# time-module.net
KiCad netlist of a schematic drawn in EAGLE
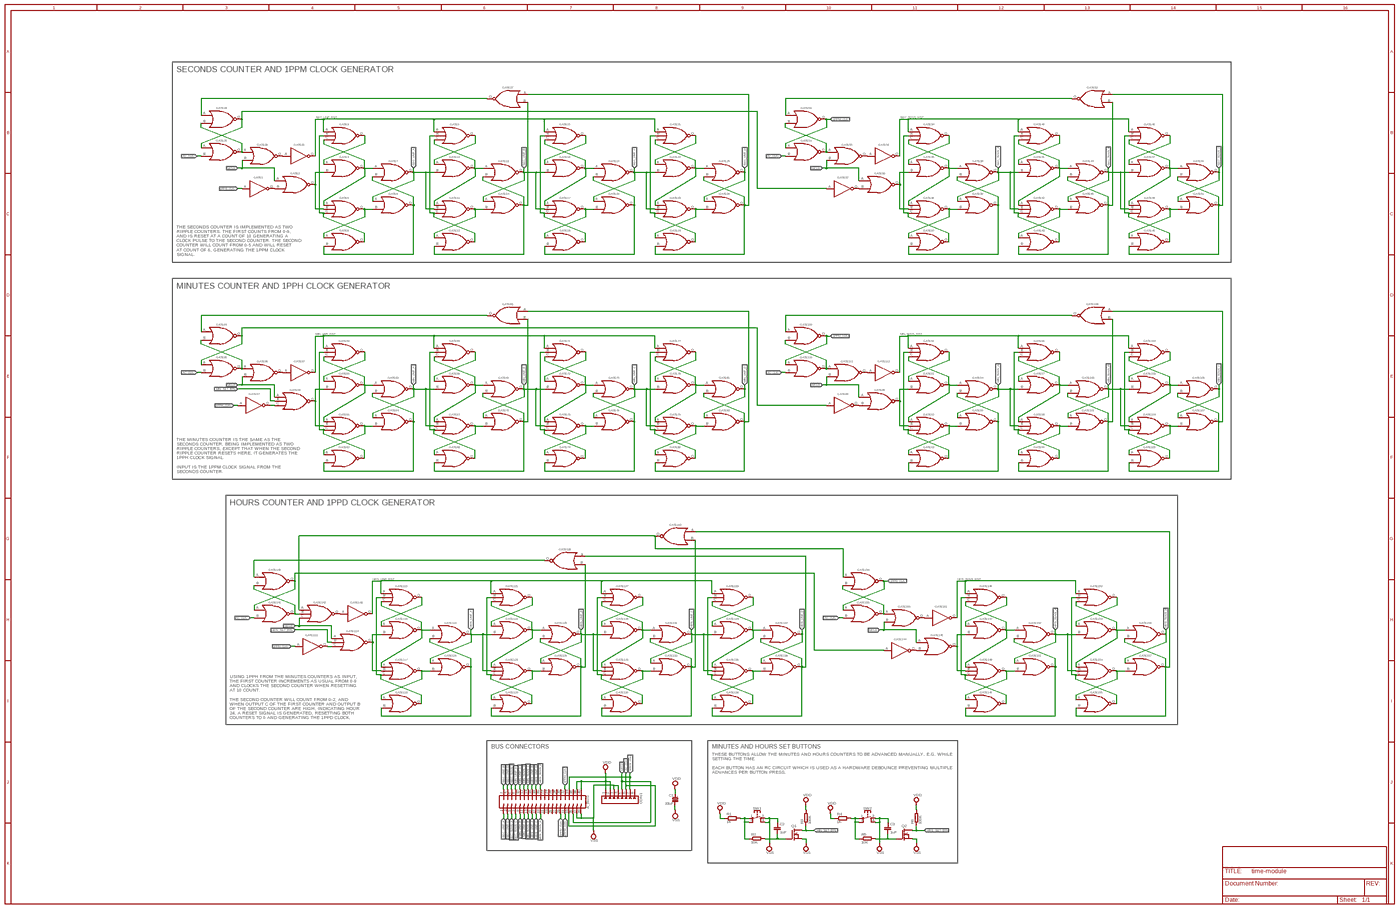
[diagram p0: schematic, sheet 1, overview]
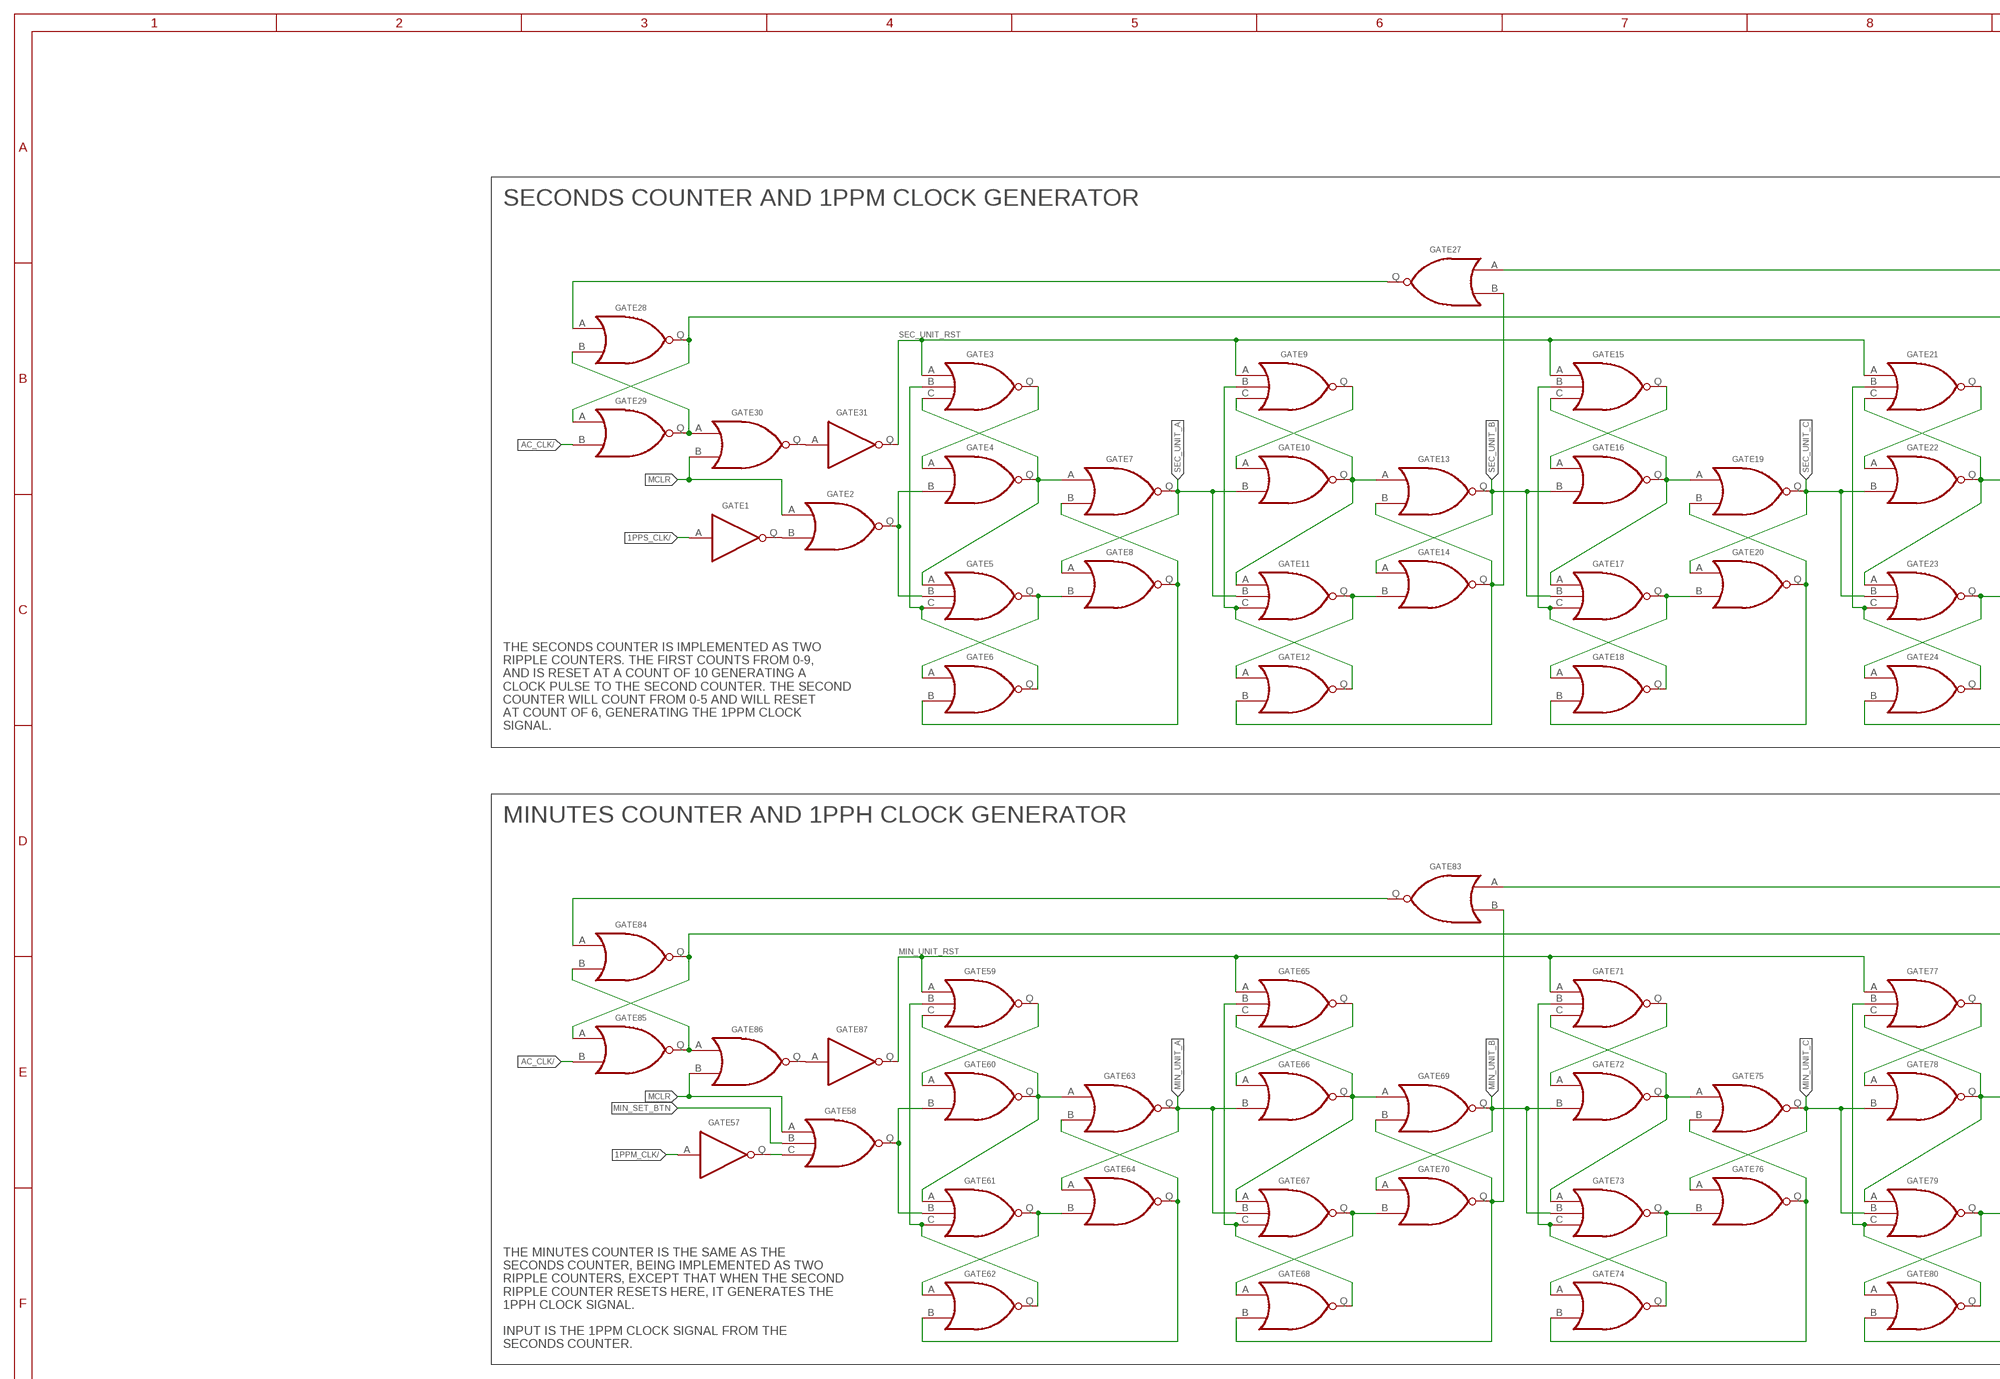
[diagram p1: schematic, sheet 1, part 1 of 4]
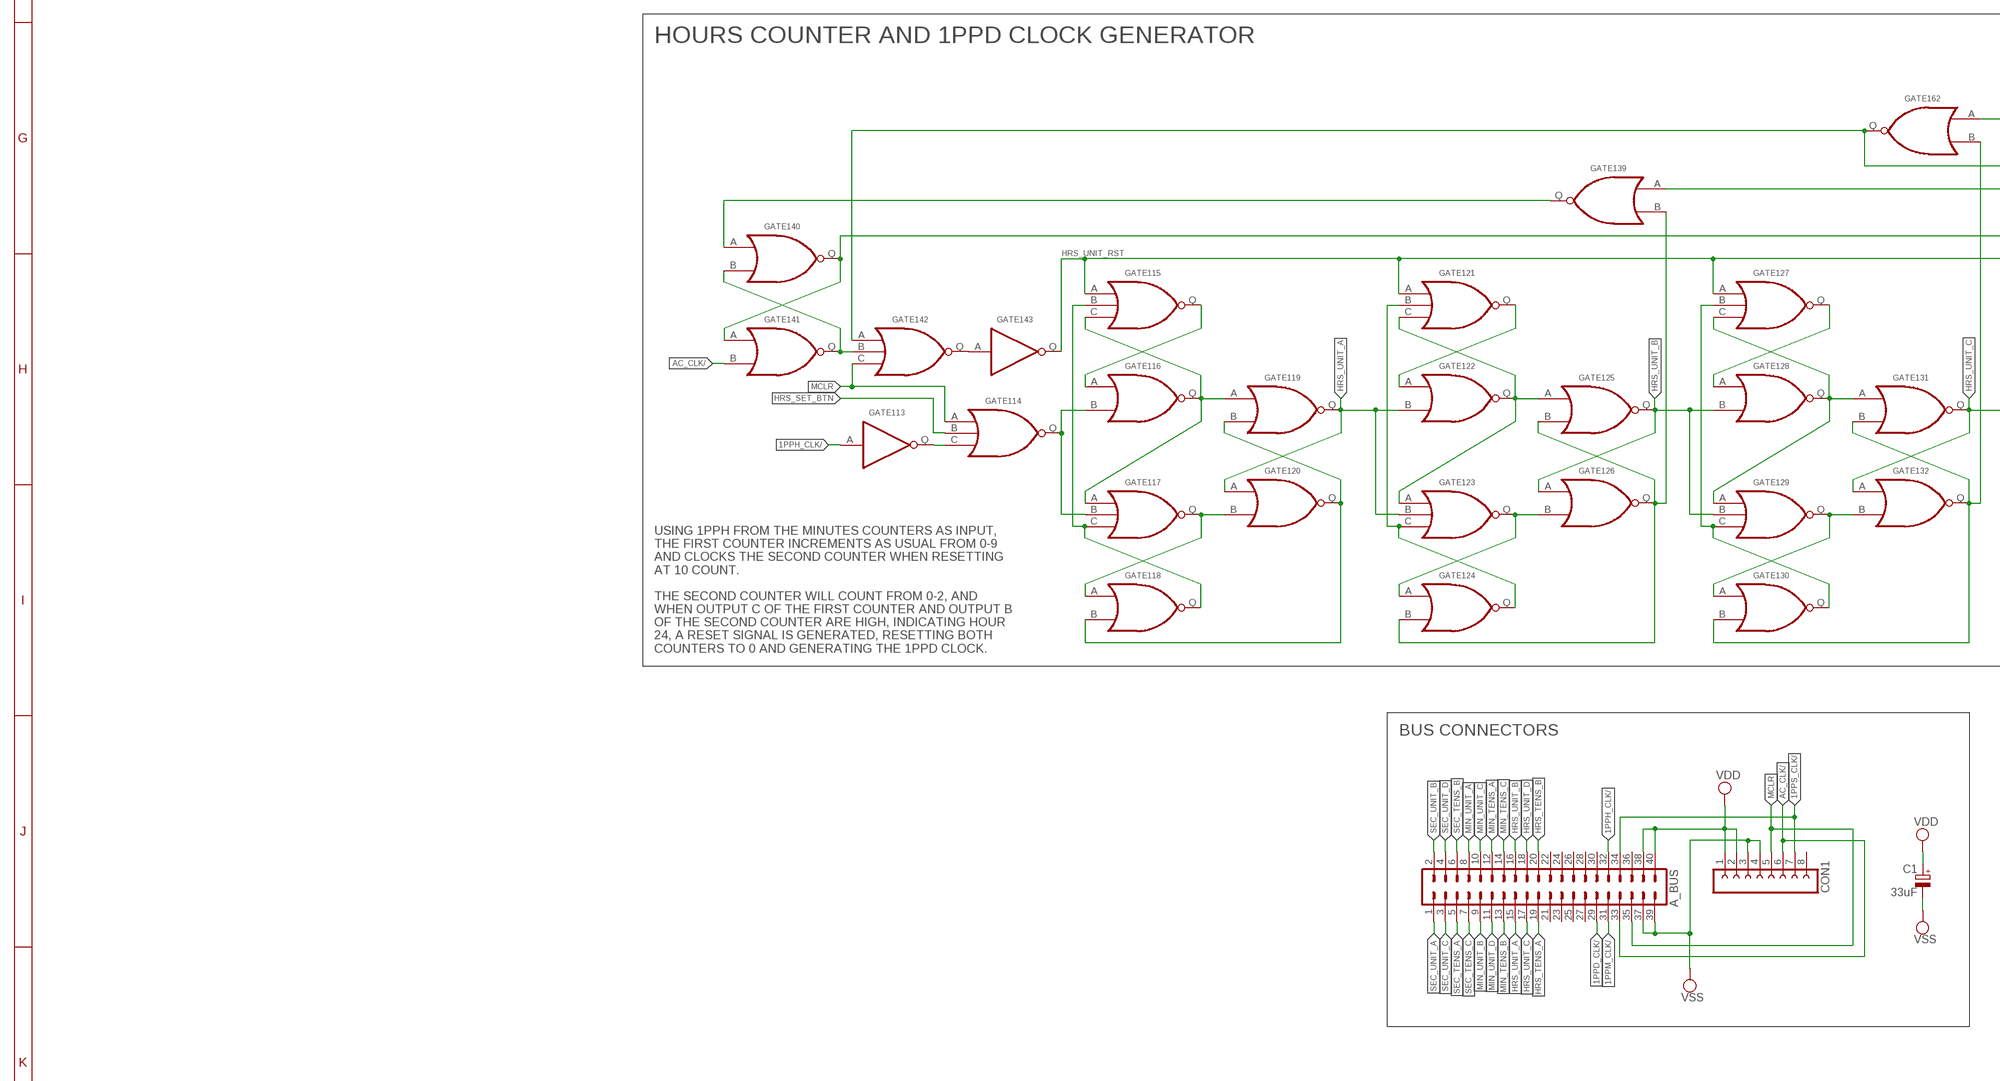
[diagram p2: schematic, sheet 1, part 2 of 4]
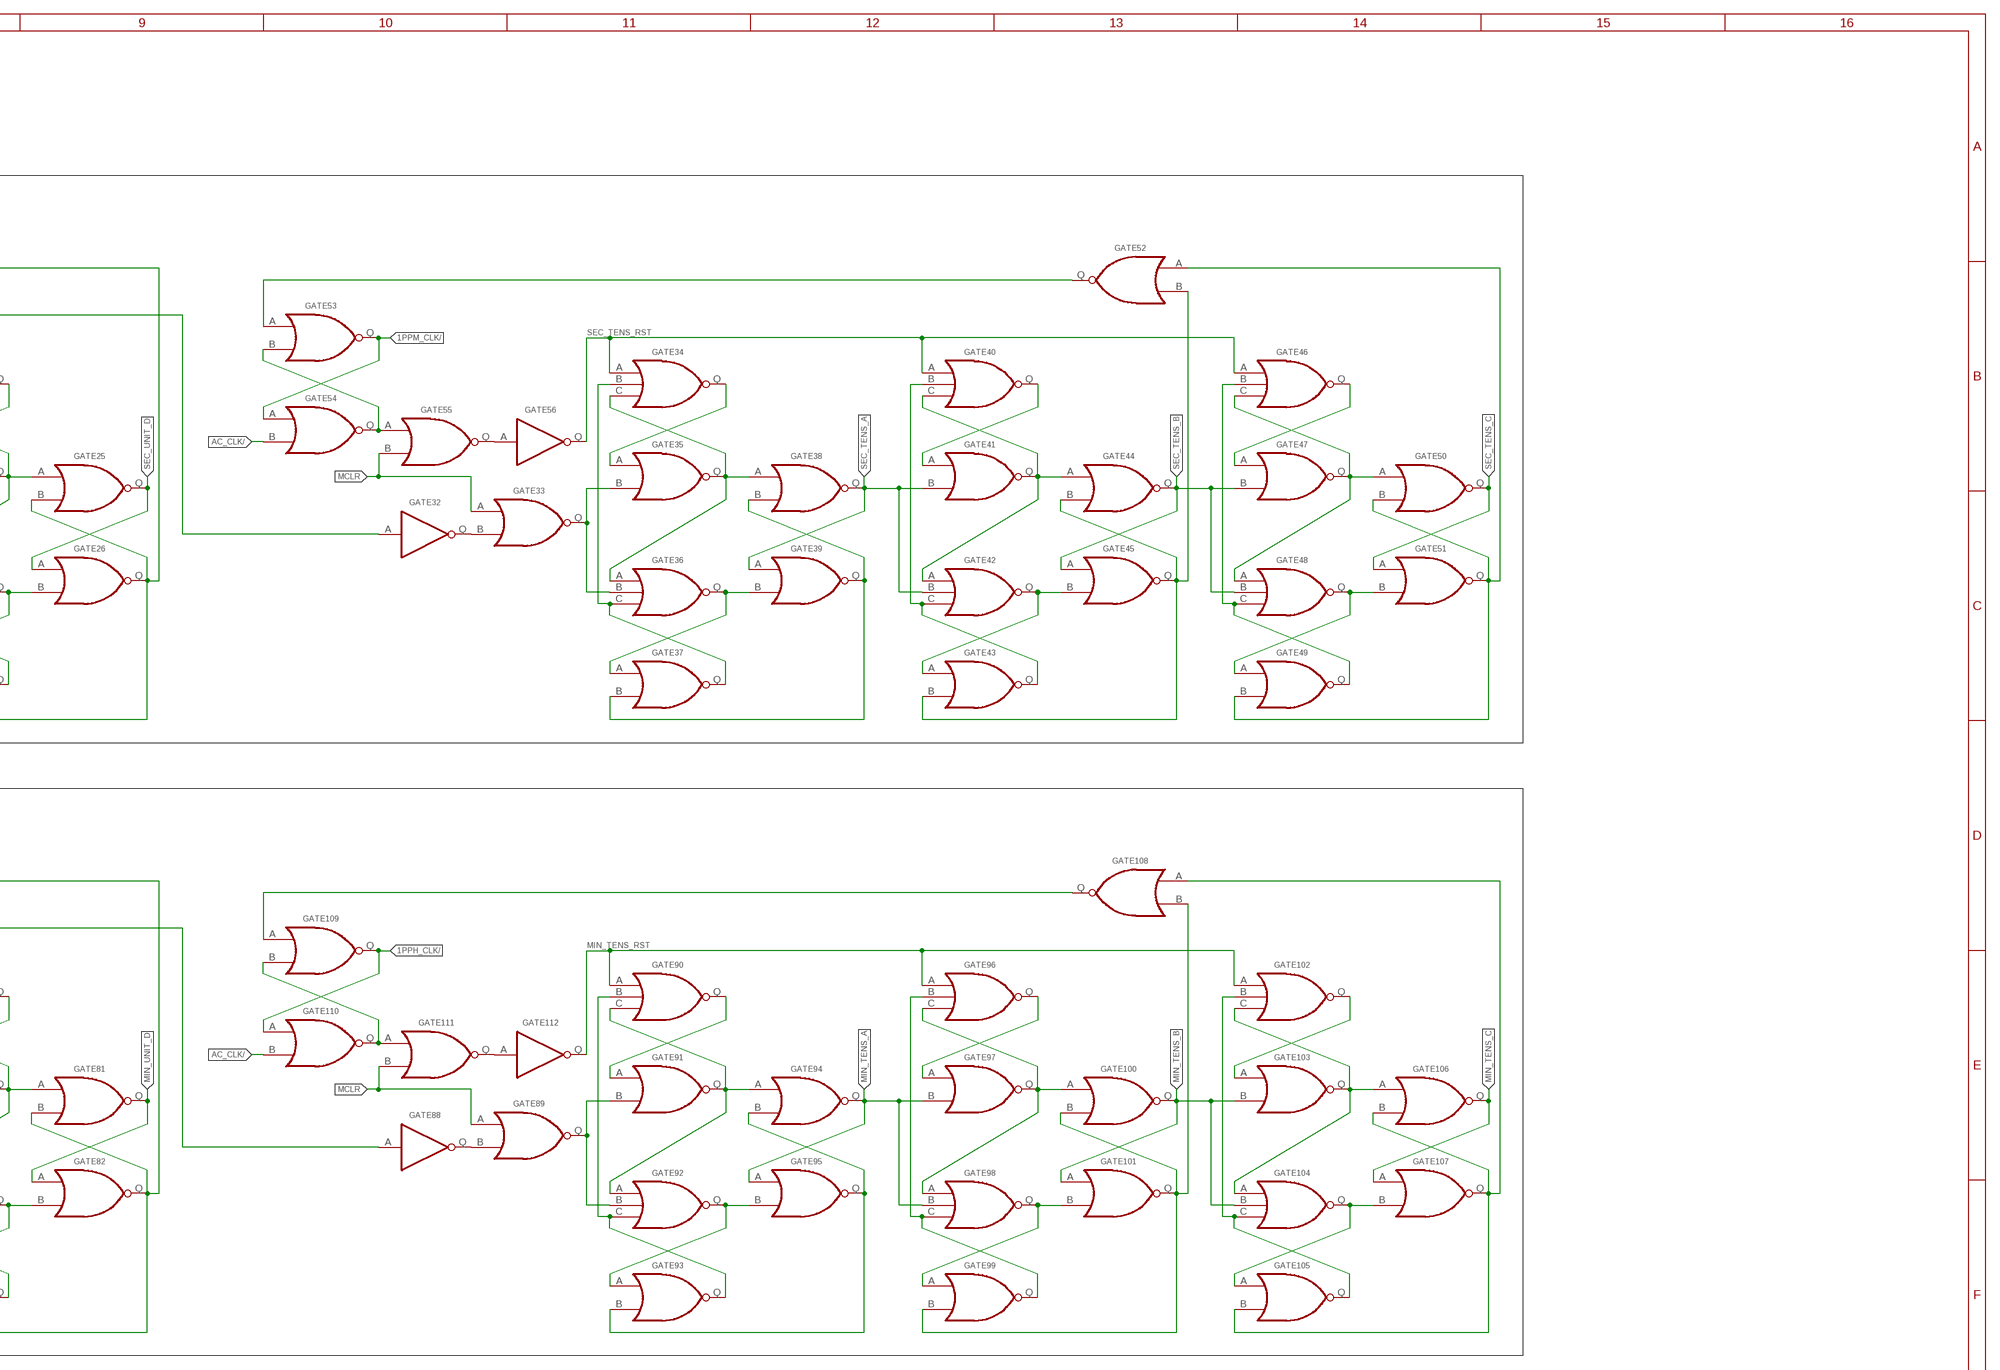
[diagram p3: schematic, sheet 1, part 3 of 4]
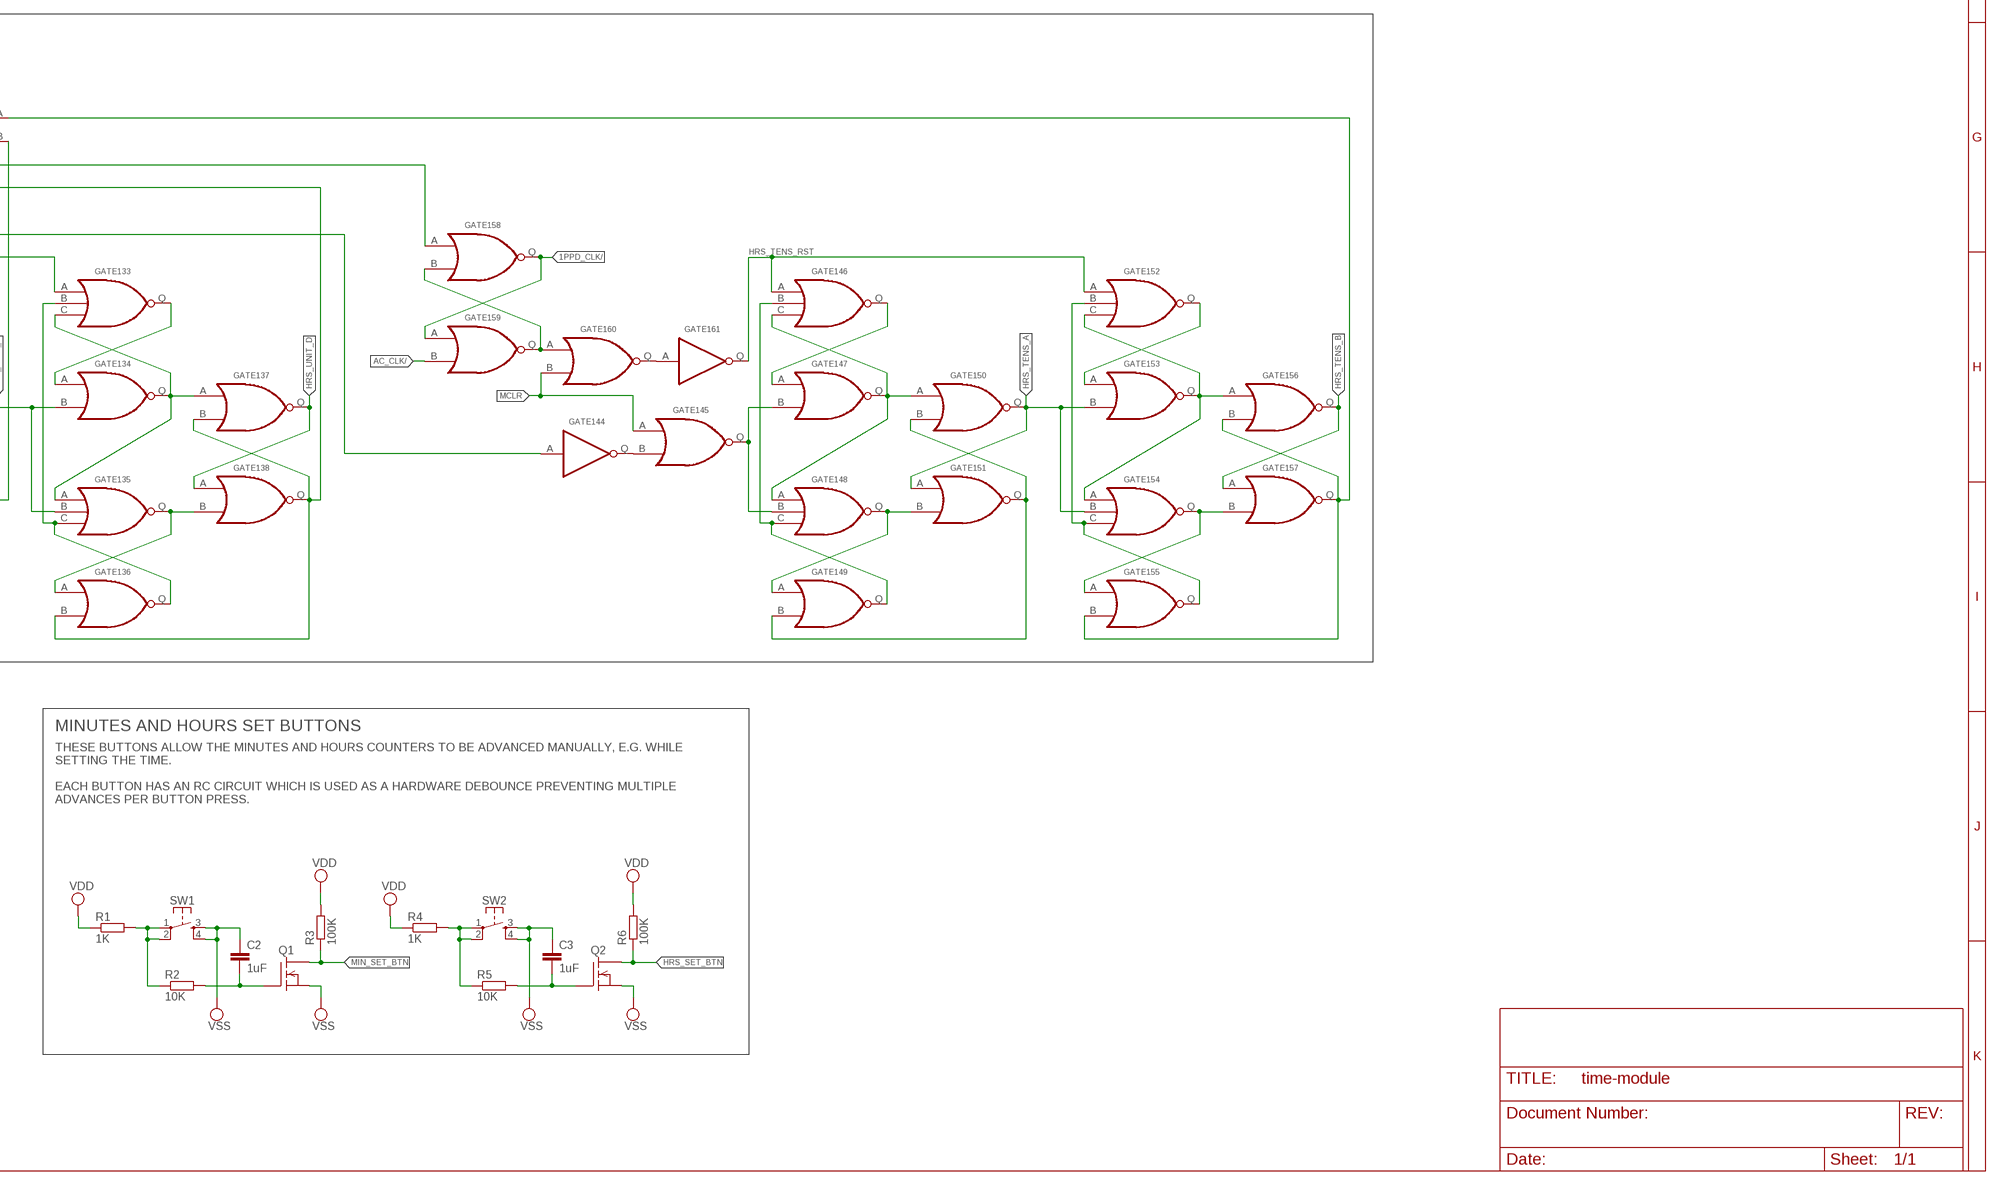
[diagram p4: schematic, sheet 1, part 4 of 4]

(export (version "E")
  (design (tool "Eeschema 10.0.6"))
  (components
    (comp (ref "A_BUS")
      (value "MA20-2")
      (footprint "eagle-import:MA20-2")
      (libsource (lib "eagle-import") (part "MA20-2"))
    )
    (comp (ref "C1")
      (value "33uF")
      (footprint "eagle-import:E2,5-6")
      (libsource (lib "eagle-import") (part "CPOL-EUE2.5-6"))
    )
    (comp (ref "C2")
      (value "1uF")
      (footprint "eagle-import:C050-025X075")
      (libsource (lib "eagle-import") (part "C-EU050-025X075"))
    )
    (comp (ref "C3")
      (value "1uF")
      (footprint "eagle-import:C050-025X075")
      (libsource (lib "eagle-import") (part "C-EU050-025X075"))
    )
    (comp (ref "CON1")
      (value "FE08-1")
      (footprint "eagle-import:FE08")
      (libsource (lib "eagle-import") (part "FE08-1"))
    )
    (comp (ref "GATE1")
      (value "INVERTER")
      (footprint "eagle-import:INVERTER")
      (libsource (lib "eagle-import") (part "INVERTER"))
    )
    (comp (ref "GATE2")
      (value "2NOR")
      (footprint "eagle-import:2NOR")
      (libsource (lib "eagle-import") (part "2NOR"))
    )
    (comp (ref "GATE3")
      (value "3NOR")
      (footprint "eagle-import:3NOR")
      (libsource (lib "eagle-import") (part "3NOR"))
    )
    (comp (ref "GATE4")
      (value "2NOR")
      (footprint "eagle-import:2NOR")
      (libsource (lib "eagle-import") (part "2NOR"))
    )
    (comp (ref "GATE5")
      (value "3NOR")
      (footprint "eagle-import:3NOR")
      (libsource (lib "eagle-import") (part "3NOR"))
    )
    (comp (ref "GATE6")
      (value "2NOR")
      (footprint "eagle-import:2NOR")
      (libsource (lib "eagle-import") (part "2NOR"))
    )
    (comp (ref "GATE7")
      (value "2NOR")
      (footprint "eagle-import:2NOR")
      (libsource (lib "eagle-import") (part "2NOR"))
    )
    (comp (ref "GATE8")
      (value "2NOR")
      (footprint "eagle-import:2NOR")
      (libsource (lib "eagle-import") (part "2NOR"))
    )
    (comp (ref "GATE9")
      (value "3NOR")
      (footprint "eagle-import:3NOR")
      (libsource (lib "eagle-import") (part "3NOR"))
    )
    (comp (ref "GATE10")
      (value "2NOR")
      (footprint "eagle-import:2NOR")
      (libsource (lib "eagle-import") (part "2NOR"))
    )
    (comp (ref "GATE11")
      (value "3NOR")
      (footprint "eagle-import:3NOR")
      (libsource (lib "eagle-import") (part "3NOR"))
    )
    (comp (ref "GATE12")
      (value "2NOR")
      (footprint "eagle-import:2NOR")
      (libsource (lib "eagle-import") (part "2NOR"))
    )
    (comp (ref "GATE13")
      (value "2NOR")
      (footprint "eagle-import:2NOR")
      (libsource (lib "eagle-import") (part "2NOR"))
    )
    (comp (ref "GATE14")
      (value "2NOR")
      (footprint "eagle-import:2NOR")
      (libsource (lib "eagle-import") (part "2NOR"))
    )
    (comp (ref "GATE15")
      (value "3NOR")
      (footprint "eagle-import:3NOR")
      (libsource (lib "eagle-import") (part "3NOR"))
    )
    (comp (ref "GATE16")
      (value "2NOR")
      (footprint "eagle-import:2NOR")
      (libsource (lib "eagle-import") (part "2NOR"))
    )
    (comp (ref "GATE17")
      (value "3NOR")
      (footprint "eagle-import:3NOR")
      (libsource (lib "eagle-import") (part "3NOR"))
    )
    (comp (ref "GATE18")
      (value "2NOR")
      (footprint "eagle-import:2NOR")
      (libsource (lib "eagle-import") (part "2NOR"))
    )
    (comp (ref "GATE19")
      (value "2NOR")
      (footprint "eagle-import:2NOR")
      (libsource (lib "eagle-import") (part "2NOR"))
    )
    (comp (ref "GATE20")
      (value "2NOR")
      (footprint "eagle-import:2NOR")
      (libsource (lib "eagle-import") (part "2NOR"))
    )
    (comp (ref "GATE21")
      (value "3NOR")
      (footprint "eagle-import:3NOR")
      (libsource (lib "eagle-import") (part "3NOR"))
    )
    (comp (ref "GATE22")
      (value "2NOR")
      (footprint "eagle-import:2NOR")
      (libsource (lib "eagle-import") (part "2NOR"))
    )
    (comp (ref "GATE23")
      (value "3NOR")
      (footprint "eagle-import:3NOR")
      (libsource (lib "eagle-import") (part "3NOR"))
    )
    (comp (ref "GATE24")
      (value "2NOR")
      (footprint "eagle-import:2NOR")
      (libsource (lib "eagle-import") (part "2NOR"))
    )
    (comp (ref "GATE25")
      (value "2NOR")
      (footprint "eagle-import:2NOR")
      (libsource (lib "eagle-import") (part "2NOR"))
    )
    (comp (ref "GATE26")
      (value "2NOR")
      (footprint "eagle-import:2NOR")
      (libsource (lib "eagle-import") (part "2NOR"))
    )
    (comp (ref "GATE27")
      (value "2NOR")
      (footprint "eagle-import:2NOR")
      (libsource (lib "eagle-import") (part "2NOR"))
    )
    (comp (ref "GATE28")
      (value "2NOR")
      (footprint "eagle-import:2NOR")
      (libsource (lib "eagle-import") (part "2NOR"))
    )
    (comp (ref "GATE29")
      (value "2NOR")
      (footprint "eagle-import:2NOR")
      (libsource (lib "eagle-import") (part "2NOR"))
    )
    (comp (ref "GATE30")
      (value "2NOR")
      (footprint "eagle-import:2NOR")
      (libsource (lib "eagle-import") (part "2NOR"))
    )
    (comp (ref "GATE31")
      (value "INVERTER")
      (footprint "eagle-import:INVERTER")
      (libsource (lib "eagle-import") (part "INVERTER"))
    )
    (comp (ref "GATE32")
      (value "INVERTER")
      (footprint "eagle-import:INVERTER")
      (libsource (lib "eagle-import") (part "INVERTER"))
    )
    (comp (ref "GATE33")
      (value "2NOR")
      (footprint "eagle-import:2NOR")
      (libsource (lib "eagle-import") (part "2NOR"))
    )
    (comp (ref "GATE34")
      (value "3NOR")
      (footprint "eagle-import:3NOR")
      (libsource (lib "eagle-import") (part "3NOR"))
    )
    (comp (ref "GATE35")
      (value "2NOR")
      (footprint "eagle-import:2NOR")
      (libsource (lib "eagle-import") (part "2NOR"))
    )
    (comp (ref "GATE36")
      (value "3NOR")
      (footprint "eagle-import:3NOR")
      (libsource (lib "eagle-import") (part "3NOR"))
    )
    (comp (ref "GATE37")
      (value "2NOR")
      (footprint "eagle-import:2NOR")
      (libsource (lib "eagle-import") (part "2NOR"))
    )
    (comp (ref "GATE38")
      (value "2NOR")
      (footprint "eagle-import:2NOR")
      (libsource (lib "eagle-import") (part "2NOR"))
    )
    (comp (ref "GATE39")
      (value "2NOR")
      (footprint "eagle-import:2NOR")
      (libsource (lib "eagle-import") (part "2NOR"))
    )
    (comp (ref "GATE40")
      (value "3NOR")
      (footprint "eagle-import:3NOR")
      (libsource (lib "eagle-import") (part "3NOR"))
    )
    (comp (ref "GATE41")
      (value "2NOR")
      (footprint "eagle-import:2NOR")
      (libsource (lib "eagle-import") (part "2NOR"))
    )
    (comp (ref "GATE42")
      (value "3NOR")
      (footprint "eagle-import:3NOR")
      (libsource (lib "eagle-import") (part "3NOR"))
    )
    (comp (ref "GATE43")
      (value "2NOR")
      (footprint "eagle-import:2NOR")
      (libsource (lib "eagle-import") (part "2NOR"))
    )
    (comp (ref "GATE44")
      (value "2NOR")
      (footprint "eagle-import:2NOR")
      (libsource (lib "eagle-import") (part "2NOR"))
    )
    (comp (ref "GATE45")
      (value "2NOR")
      (footprint "eagle-import:2NOR")
      (libsource (lib "eagle-import") (part "2NOR"))
    )
    (comp (ref "GATE46")
      (value "3NOR")
      (footprint "eagle-import:3NOR")
      (libsource (lib "eagle-import") (part "3NOR"))
    )
    (comp (ref "GATE47")
      (value "2NOR")
      (footprint "eagle-import:2NOR")
      (libsource (lib "eagle-import") (part "2NOR"))
    )
    (comp (ref "GATE48")
      (value "3NOR")
      (footprint "eagle-import:3NOR")
      (libsource (lib "eagle-import") (part "3NOR"))
    )
    (comp (ref "GATE49")
      (value "2NOR")
      (footprint "eagle-import:2NOR")
      (libsource (lib "eagle-import") (part "2NOR"))
    )
    (comp (ref "GATE50")
      (value "2NOR")
      (footprint "eagle-import:2NOR")
      (libsource (lib "eagle-import") (part "2NOR"))
    )
    (comp (ref "GATE51")
      (value "2NOR")
      (footprint "eagle-import:2NOR")
      (libsource (lib "eagle-import") (part "2NOR"))
    )
    (comp (ref "GATE52")
      (value "2NOR")
      (footprint "eagle-import:2NOR")
      (libsource (lib "eagle-import") (part "2NOR"))
    )
    (comp (ref "GATE53")
      (value "2NOR")
      (footprint "eagle-import:2NOR")
      (libsource (lib "eagle-import") (part "2NOR"))
    )
    (comp (ref "GATE54")
      (value "2NOR")
      (footprint "eagle-import:2NOR")
      (libsource (lib "eagle-import") (part "2NOR"))
    )
    (comp (ref "GATE55")
      (value "2NOR")
      (footprint "eagle-import:2NOR")
      (libsource (lib "eagle-import") (part "2NOR"))
    )
    (comp (ref "GATE56")
      (value "INVERTER")
      (footprint "eagle-import:INVERTER")
      (libsource (lib "eagle-import") (part "INVERTER"))
    )
    (comp (ref "GATE57")
      (value "INVERTER")
      (footprint "eagle-import:INVERTER")
      (libsource (lib "eagle-import") (part "INVERTER"))
    )
    (comp (ref "GATE58")
      (value "3NOR")
      (footprint "eagle-import:3NOR")
      (libsource (lib "eagle-import") (part "3NOR"))
    )
    (comp (ref "GATE59")
      (value "3NOR")
      (footprint "eagle-import:3NOR")
      (libsource (lib "eagle-import") (part "3NOR"))
    )
    (comp (ref "GATE60")
      (value "2NOR")
      (footprint "eagle-import:2NOR")
      (libsource (lib "eagle-import") (part "2NOR"))
    )
    (comp (ref "GATE61")
      (value "3NOR")
      (footprint "eagle-import:3NOR")
      (libsource (lib "eagle-import") (part "3NOR"))
    )
    (comp (ref "GATE62")
      (value "2NOR")
      (footprint "eagle-import:2NOR")
      (libsource (lib "eagle-import") (part "2NOR"))
    )
    (comp (ref "GATE63")
      (value "2NOR")
      (footprint "eagle-import:2NOR")
      (libsource (lib "eagle-import") (part "2NOR"))
    )
    (comp (ref "GATE64")
      (value "2NOR")
      (footprint "eagle-import:2NOR")
      (libsource (lib "eagle-import") (part "2NOR"))
    )
    (comp (ref "GATE65")
      (value "3NOR")
      (footprint "eagle-import:3NOR")
      (libsource (lib "eagle-import") (part "3NOR"))
    )
    (comp (ref "GATE66")
      (value "2NOR")
      (footprint "eagle-import:2NOR")
      (libsource (lib "eagle-import") (part "2NOR"))
    )
    (comp (ref "GATE67")
      (value "3NOR")
      (footprint "eagle-import:3NOR")
      (libsource (lib "eagle-import") (part "3NOR"))
    )
    (comp (ref "GATE68")
      (value "2NOR")
      (footprint "eagle-import:2NOR")
      (libsource (lib "eagle-import") (part "2NOR"))
    )
    (comp (ref "GATE69")
      (value "2NOR")
      (footprint "eagle-import:2NOR")
      (libsource (lib "eagle-import") (part "2NOR"))
    )
    (comp (ref "GATE70")
      (value "2NOR")
      (footprint "eagle-import:2NOR")
      (libsource (lib "eagle-import") (part "2NOR"))
    )
    (comp (ref "GATE71")
      (value "3NOR")
      (footprint "eagle-import:3NOR")
      (libsource (lib "eagle-import") (part "3NOR"))
    )
    (comp (ref "GATE72")
      (value "2NOR")
      (footprint "eagle-import:2NOR")
      (libsource (lib "eagle-import") (part "2NOR"))
    )
    (comp (ref "GATE73")
      (value "3NOR")
      (footprint "eagle-import:3NOR")
      (libsource (lib "eagle-import") (part "3NOR"))
    )
    (comp (ref "GATE74")
      (value "2NOR")
      (footprint "eagle-import:2NOR")
      (libsource (lib "eagle-import") (part "2NOR"))
    )
    (comp (ref "GATE75")
      (value "2NOR")
      (footprint "eagle-import:2NOR")
      (libsource (lib "eagle-import") (part "2NOR"))
    )
    (comp (ref "GATE76")
      (value "2NOR")
      (footprint "eagle-import:2NOR")
      (libsource (lib "eagle-import") (part "2NOR"))
    )
    (comp (ref "GATE77")
      (value "3NOR")
      (footprint "eagle-import:3NOR")
      (libsource (lib "eagle-import") (part "3NOR"))
    )
    (comp (ref "GATE78")
      (value "2NOR")
      (footprint "eagle-import:2NOR")
      (libsource (lib "eagle-import") (part "2NOR"))
    )
    (comp (ref "GATE79")
      (value "3NOR")
      (footprint "eagle-import:3NOR")
      (libsource (lib "eagle-import") (part "3NOR"))
    )
    (comp (ref "GATE80")
      (value "2NOR")
      (footprint "eagle-import:2NOR")
      (libsource (lib "eagle-import") (part "2NOR"))
    )
    (comp (ref "GATE81")
      (value "2NOR")
      (footprint "eagle-import:2NOR")
      (libsource (lib "eagle-import") (part "2NOR"))
    )
    (comp (ref "GATE82")
      (value "2NOR")
      (footprint "eagle-import:2NOR")
      (libsource (lib "eagle-import") (part "2NOR"))
    )
    (comp (ref "GATE83")
      (value "2NOR")
      (footprint "eagle-import:2NOR")
      (libsource (lib "eagle-import") (part "2NOR"))
    )
    (comp (ref "GATE84")
      (value "2NOR")
      (footprint "eagle-import:2NOR")
      (libsource (lib "eagle-import") (part "2NOR"))
    )
    (comp (ref "GATE85")
      (value "2NOR")
      (footprint "eagle-import:2NOR")
      (libsource (lib "eagle-import") (part "2NOR"))
    )
    (comp (ref "GATE86")
      (value "2NOR")
      (footprint "eagle-import:2NOR")
      (libsource (lib "eagle-import") (part "2NOR"))
    )
    (comp (ref "GATE87")
      (value "INVERTER")
      (footprint "eagle-import:INVERTER")
      (libsource (lib "eagle-import") (part "INVERTER"))
    )
    (comp (ref "GATE88")
      (value "INVERTER")
      (footprint "eagle-import:INVERTER")
      (libsource (lib "eagle-import") (part "INVERTER"))
    )
    (comp (ref "GATE89")
      (value "2NOR")
      (footprint "eagle-import:2NOR")
      (libsource (lib "eagle-import") (part "2NOR"))
    )
    (comp (ref "GATE90")
      (value "3NOR")
      (footprint "eagle-import:3NOR")
      (libsource (lib "eagle-import") (part "3NOR"))
    )
    (comp (ref "GATE91")
      (value "2NOR")
      (footprint "eagle-import:2NOR")
      (libsource (lib "eagle-import") (part "2NOR"))
    )
    (comp (ref "GATE92")
      (value "3NOR")
      (footprint "eagle-import:3NOR")
      (libsource (lib "eagle-import") (part "3NOR"))
    )
    (comp (ref "GATE93")
      (value "2NOR")
      (footprint "eagle-import:2NOR")
      (libsource (lib "eagle-import") (part "2NOR"))
    )
    (comp (ref "GATE94")
      (value "2NOR")
      (footprint "eagle-import:2NOR")
      (libsource (lib "eagle-import") (part "2NOR"))
    )
    (comp (ref "GATE95")
      (value "2NOR")
      (footprint "eagle-import:2NOR")
      (libsource (lib "eagle-import") (part "2NOR"))
    )
    (comp (ref "GATE96")
      (value "3NOR")
      (footprint "eagle-import:3NOR")
      (libsource (lib "eagle-import") (part "3NOR"))
    )
    (comp (ref "GATE97")
      (value "2NOR")
      (footprint "eagle-import:2NOR")
      (libsource (lib "eagle-import") (part "2NOR"))
    )
    (comp (ref "GATE98")
      (value "3NOR")
      (footprint "eagle-import:3NOR")
      (libsource (lib "eagle-import") (part "3NOR"))
    )
    (comp (ref "GATE99")
      (value "2NOR")
      (footprint "eagle-import:2NOR")
      (libsource (lib "eagle-import") (part "2NOR"))
    )
    (comp (ref "GATE100")
      (value "2NOR")
      (footprint "eagle-import:2NOR")
      (libsource (lib "eagle-import") (part "2NOR"))
    )
    (comp (ref "GATE101")
      (value "2NOR")
      (footprint "eagle-import:2NOR")
      (libsource (lib "eagle-import") (part "2NOR"))
    )
    (comp (ref "GATE102")
      (value "3NOR")
      (footprint "eagle-import:3NOR")
      (libsource (lib "eagle-import") (part "3NOR"))
    )
    (comp (ref "GATE103")
      (value "2NOR")
      (footprint "eagle-import:2NOR")
      (libsource (lib "eagle-import") (part "2NOR"))
    )
    (comp (ref "GATE104")
      (value "3NOR")
      (footprint "eagle-import:3NOR")
      (libsource (lib "eagle-import") (part "3NOR"))
    )
    (comp (ref "GATE105")
      (value "2NOR")
      (footprint "eagle-import:2NOR")
      (libsource (lib "eagle-import") (part "2NOR"))
    )
    (comp (ref "GATE106")
      (value "2NOR")
      (footprint "eagle-import:2NOR")
      (libsource (lib "eagle-import") (part "2NOR"))
    )
    (comp (ref "GATE107")
      (value "2NOR")
      (footprint "eagle-import:2NOR")
      (libsource (lib "eagle-import") (part "2NOR"))
    )
    (comp (ref "GATE108")
      (value "2NOR")
      (footprint "eagle-import:2NOR")
      (libsource (lib "eagle-import") (part "2NOR"))
    )
    (comp (ref "GATE109")
      (value "2NOR")
      (footprint "eagle-import:2NOR")
      (libsource (lib "eagle-import") (part "2NOR"))
    )
    (comp (ref "GATE110")
      (value "2NOR")
      (footprint "eagle-import:2NOR")
      (libsource (lib "eagle-import") (part "2NOR"))
    )
    (comp (ref "GATE111")
      (value "2NOR")
      (footprint "eagle-import:2NOR")
      (libsource (lib "eagle-import") (part "2NOR"))
    )
    (comp (ref "GATE112")
      (value "INVERTER")
      (footprint "eagle-import:INVERTER")
      (libsource (lib "eagle-import") (part "INVERTER"))
    )
    (comp (ref "GATE113")
      (value "INVERTER")
      (footprint "eagle-import:INVERTER")
      (libsource (lib "eagle-import") (part "INVERTER"))
    )
    (comp (ref "GATE114")
      (value "3NOR")
      (footprint "eagle-import:3NOR")
      (libsource (lib "eagle-import") (part "3NOR"))
    )
    (comp (ref "GATE115")
      (value "3NOR")
      (footprint "eagle-import:3NOR")
      (libsource (lib "eagle-import") (part "3NOR"))
    )
    (comp (ref "GATE116")
      (value "2NOR")
      (footprint "eagle-import:2NOR")
      (libsource (lib "eagle-import") (part "2NOR"))
    )
    (comp (ref "GATE117")
      (value "3NOR")
      (footprint "eagle-import:3NOR")
      (libsource (lib "eagle-import") (part "3NOR"))
    )
    (comp (ref "GATE118")
      (value "2NOR")
      (footprint "eagle-import:2NOR")
      (libsource (lib "eagle-import") (part "2NOR"))
    )
    (comp (ref "GATE119")
      (value "2NOR")
      (footprint "eagle-import:2NOR")
      (libsource (lib "eagle-import") (part "2NOR"))
    )
    (comp (ref "GATE120")
      (value "2NOR")
      (footprint "eagle-import:2NOR")
      (libsource (lib "eagle-import") (part "2NOR"))
    )
    (comp (ref "GATE121")
      (value "3NOR")
      (footprint "eagle-import:3NOR")
      (libsource (lib "eagle-import") (part "3NOR"))
    )
    (comp (ref "GATE122")
      (value "2NOR")
      (footprint "eagle-import:2NOR")
      (libsource (lib "eagle-import") (part "2NOR"))
    )
    (comp (ref "GATE123")
      (value "3NOR")
      (footprint "eagle-import:3NOR")
      (libsource (lib "eagle-import") (part "3NOR"))
    )
    (comp (ref "GATE124")
      (value "2NOR")
      (footprint "eagle-import:2NOR")
      (libsource (lib "eagle-import") (part "2NOR"))
    )
    (comp (ref "GATE125")
      (value "2NOR")
      (footprint "eagle-import:2NOR")
      (libsource (lib "eagle-import") (part "2NOR"))
    )
    (comp (ref "GATE126")
      (value "2NOR")
      (footprint "eagle-import:2NOR")
      (libsource (lib "eagle-import") (part "2NOR"))
    )
    (comp (ref "GATE127")
      (value "3NOR")
      (footprint "eagle-import:3NOR")
      (libsource (lib "eagle-import") (part "3NOR"))
    )
    (comp (ref "GATE128")
      (value "2NOR")
      (footprint "eagle-import:2NOR")
      (libsource (lib "eagle-import") (part "2NOR"))
    )
    (comp (ref "GATE129")
      (value "3NOR")
      (footprint "eagle-import:3NOR")
      (libsource (lib "eagle-import") (part "3NOR"))
    )
    (comp (ref "GATE130")
      (value "2NOR")
      (footprint "eagle-import:2NOR")
      (libsource (lib "eagle-import") (part "2NOR"))
    )
    (comp (ref "GATE131")
      (value "2NOR")
      (footprint "eagle-import:2NOR")
      (libsource (lib "eagle-import") (part "2NOR"))
    )
    (comp (ref "GATE132")
      (value "2NOR")
      (footprint "eagle-import:2NOR")
      (libsource (lib "eagle-import") (part "2NOR"))
    )
    (comp (ref "GATE133")
      (value "3NOR")
      (footprint "eagle-import:3NOR")
      (libsource (lib "eagle-import") (part "3NOR"))
    )
    (comp (ref "GATE134")
      (value "2NOR")
      (footprint "eagle-import:2NOR")
      (libsource (lib "eagle-import") (part "2NOR"))
    )
    (comp (ref "GATE135")
      (value "3NOR")
      (footprint "eagle-import:3NOR")
      (libsource (lib "eagle-import") (part "3NOR"))
    )
    (comp (ref "GATE136")
      (value "2NOR")
      (footprint "eagle-import:2NOR")
      (libsource (lib "eagle-import") (part "2NOR"))
    )
    (comp (ref "GATE137")
      (value "2NOR")
      (footprint "eagle-import:2NOR")
      (libsource (lib "eagle-import") (part "2NOR"))
    )
    (comp (ref "GATE138")
      (value "2NOR")
      (footprint "eagle-import:2NOR")
      (libsource (lib "eagle-import") (part "2NOR"))
    )
    (comp (ref "GATE139")
      (value "2NOR")
      (footprint "eagle-import:2NOR")
      (libsource (lib "eagle-import") (part "2NOR"))
    )
    (comp (ref "GATE140")
      (value "2NOR")
      (footprint "eagle-import:2NOR")
      (libsource (lib "eagle-import") (part "2NOR"))
    )
    (comp (ref "GATE141")
      (value "2NOR")
      (footprint "eagle-import:2NOR")
      (libsource (lib "eagle-import") (part "2NOR"))
    )
    (comp (ref "GATE142")
      (value "3NOR")
      (footprint "eagle-import:3NOR")
      (libsource (lib "eagle-import") (part "3NOR"))
    )
    (comp (ref "GATE143")
      (value "INVERTER")
      (footprint "eagle-import:INVERTER")
      (libsource (lib "eagle-import") (part "INVERTER"))
    )
    (comp (ref "GATE144")
      (value "INVERTER")
      (footprint "eagle-import:INVERTER")
      (libsource (lib "eagle-import") (part "INVERTER"))
    )
    (comp (ref "GATE145")
      (value "2NOR")
      (footprint "eagle-import:2NOR")
      (libsource (lib "eagle-import") (part "2NOR"))
    )
    (comp (ref "GATE146")
      (value "3NOR")
      (footprint "eagle-import:3NOR")
      (libsource (lib "eagle-import") (part "3NOR"))
    )
    (comp (ref "GATE147")
      (value "2NOR")
      (footprint "eagle-import:2NOR")
      (libsource (lib "eagle-import") (part "2NOR"))
    )
    (comp (ref "GATE148")
      (value "3NOR")
      (footprint "eagle-import:3NOR")
      (libsource (lib "eagle-import") (part "3NOR"))
    )
    (comp (ref "GATE149")
      (value "2NOR")
      (footprint "eagle-import:2NOR")
      (libsource (lib "eagle-import") (part "2NOR"))
    )
    (comp (ref "GATE150")
      (value "2NOR")
      (footprint "eagle-import:2NOR")
      (libsource (lib "eagle-import") (part "2NOR"))
    )
    (comp (ref "GATE151")
      (value "2NOR")
      (footprint "eagle-import:2NOR")
      (libsource (lib "eagle-import") (part "2NOR"))
    )
    (comp (ref "GATE152")
      (value "3NOR")
      (footprint "eagle-import:3NOR")
      (libsource (lib "eagle-import") (part "3NOR"))
    )
    (comp (ref "GATE153")
      (value "2NOR")
      (footprint "eagle-import:2NOR")
      (libsource (lib "eagle-import") (part "2NOR"))
    )
    (comp (ref "GATE154")
      (value "3NOR")
      (footprint "eagle-import:3NOR")
      (libsource (lib "eagle-import") (part "3NOR"))
    )
    (comp (ref "GATE155")
      (value "2NOR")
      (footprint "eagle-import:2NOR")
      (libsource (lib "eagle-import") (part "2NOR"))
    )
    (comp (ref "GATE156")
      (value "2NOR")
      (footprint "eagle-import:2NOR")
      (libsource (lib "eagle-import") (part "2NOR"))
    )
    (comp (ref "GATE157")
      (value "2NOR")
      (footprint "eagle-import:2NOR")
      (libsource (lib "eagle-import") (part "2NOR"))
    )
    (comp (ref "GATE158")
      (value "2NOR")
      (footprint "eagle-import:2NOR")
      (libsource (lib "eagle-import") (part "2NOR"))
    )
    (comp (ref "GATE159")
      (value "2NOR")
      (footprint "eagle-import:2NOR")
      (libsource (lib "eagle-import") (part "2NOR"))
    )
    (comp (ref "GATE160")
      (value "2NOR")
      (footprint "eagle-import:2NOR")
      (libsource (lib "eagle-import") (part "2NOR"))
    )
    (comp (ref "GATE161")
      (value "INVERTER")
      (footprint "eagle-import:INVERTER")
      (libsource (lib "eagle-import") (part "INVERTER"))
    )
    (comp (ref "GATE162")
      (value "2NOR")
      (footprint "eagle-import:2NOR")
      (libsource (lib "eagle-import") (part "2NOR"))
    )
    (comp (ref "Q1")
      (value "2N7000")
      (footprint "eagle-import:TO-92")
      (libsource (lib "eagle-import") (part "2N7000"))
    )
    (comp (ref "Q2")
      (value "2N7000")
      (footprint "eagle-import:TO-92")
      (libsource (lib "eagle-import") (part "2N7000"))
    )
    (comp (ref "R1")
      (value "1K")
      (footprint "eagle-import:0207_2V")
      (libsource (lib "eagle-import") (part "R-EU_0207/2V"))
    )
    (comp (ref "R2")
      (value "10K")
      (footprint "eagle-import:0207_2V")
      (libsource (lib "eagle-import") (part "R-EU_0207/2V"))
    )
    (comp (ref "R3")
      (value "100K")
      (footprint "eagle-import:0207_2V")
      (libsource (lib "eagle-import") (part "R-EU_0207/2V"))
    )
    (comp (ref "R4")
      (value "1K")
      (footprint "eagle-import:0207_2V")
      (libsource (lib "eagle-import") (part "R-EU_0207/2V"))
    )
    (comp (ref "R5")
      (value "10K")
      (footprint "eagle-import:0207_2V")
      (libsource (lib "eagle-import") (part "R-EU_0207/2V"))
    )
    (comp (ref "R6")
      (value "100K")
      (footprint "eagle-import:0207_2V")
      (libsource (lib "eagle-import") (part "R-EU_0207/2V"))
    )
    (comp (ref "SW1")
      (value "SPST-TACSWITCH")
      (footprint "eagle-import:TE-SMD-TACSWITCH")
      (libsource (lib "eagle-import") (part "SPST-TACSWITCH"))
    )
    (comp (ref "SW2")
      (value "SPST-TACSWITCH")
      (footprint "eagle-import:TE-SMD-TACSWITCH")
      (libsource (lib "eagle-import") (part "SPST-TACSWITCH"))
    )
  )
  (nets
    (net (code "1") (name "/HRS_TENS_RST") (class "Default")
      (node (ref "GATE146") (pin "A") (pinfunction "A_A") (pintype "input"))
      (node (ref "GATE152") (pin "A") (pinfunction "A_A") (pintype "input"))
      (node (ref "GATE161") (pin "Q") (pinfunction "Q_Q") (pintype "output"))
    )
    (net (code "2") (name "/HRS_UNIT_RST") (class "Default")
      (node (ref "GATE115") (pin "A") (pinfunction "A_A") (pintype "input"))
      (node (ref "GATE121") (pin "A") (pinfunction "A_A") (pintype "input"))
      (node (ref "GATE127") (pin "A") (pinfunction "A_A") (pintype "input"))
      (node (ref "GATE133") (pin "A") (pinfunction "A_A") (pintype "input"))
      (node (ref "GATE143") (pin "Q") (pinfunction "Q_Q") (pintype "output"))
    )
    (net (code "3") (name "/MIN_TENS_RST") (class "Default")
      (node (ref "GATE102") (pin "A") (pinfunction "A_A") (pintype "input"))
      (node (ref "GATE112") (pin "Q") (pinfunction "Q_Q") (pintype "output"))
      (node (ref "GATE90") (pin "A") (pinfunction "A_A") (pintype "input"))
      (node (ref "GATE96") (pin "A") (pinfunction "A_A") (pintype "input"))
    )
    (net (code "4") (name "/MIN_UNIT_RST") (class "Default")
      (node (ref "GATE59") (pin "A") (pinfunction "A_A") (pintype "input"))
      (node (ref "GATE65") (pin "A") (pinfunction "A_A") (pintype "input"))
      (node (ref "GATE71") (pin "A") (pinfunction "A_A") (pintype "input"))
      (node (ref "GATE77") (pin "A") (pinfunction "A_A") (pintype "input"))
      (node (ref "GATE87") (pin "Q") (pinfunction "Q_Q") (pintype "output"))
    )
    (net (code "5") (name "/SEC_TENS_RST") (class "Default")
      (node (ref "GATE34") (pin "A") (pinfunction "A_A") (pintype "input"))
      (node (ref "GATE40") (pin "A") (pinfunction "A_A") (pintype "input"))
      (node (ref "GATE46") (pin "A") (pinfunction "A_A") (pintype "input"))
      (node (ref "GATE56") (pin "Q") (pinfunction "Q_Q") (pintype "output"))
    )
    (net (code "6") (name "/SEC_UNIT_RST") (class "Default")
      (node (ref "GATE15") (pin "A") (pinfunction "A_A") (pintype "input"))
      (node (ref "GATE21") (pin "A") (pinfunction "A_A") (pintype "input"))
      (node (ref "GATE3") (pin "A") (pinfunction "A_A") (pintype "input"))
      (node (ref "GATE31") (pin "Q") (pinfunction "Q_Q") (pintype "output"))
      (node (ref "GATE9") (pin "A") (pinfunction "A_A") (pintype "input"))
    )
    (net (code "7") (name "1PPD_CLK{slash}") (class "Default")
      (node (ref "A_BUS") (pin "29") (pinfunction "29_29") (pintype "passive"))
      (node (ref "GATE158") (pin "Q") (pinfunction "Q_Q") (pintype "output"))
      (node (ref "GATE159") (pin "A") (pinfunction "A_A") (pintype "input"))
    )
    (net (code "8") (name "1PPH_CLK{slash}") (class "Default")
      (node (ref "A_BUS") (pin "32") (pinfunction "32_32") (pintype "passive"))
      (node (ref "GATE109") (pin "Q") (pinfunction "Q_Q") (pintype "output"))
      (node (ref "GATE110") (pin "A") (pinfunction "A_A") (pintype "input"))
      (node (ref "GATE113") (pin "A") (pinfunction "A_A") (pintype "input"))
    )
    (net (code "9") (name "1PPM_CLK{slash}") (class "Default")
      (node (ref "A_BUS") (pin "31") (pinfunction "31_31") (pintype "passive"))
      (node (ref "GATE53") (pin "Q") (pinfunction "Q_Q") (pintype "output"))
      (node (ref "GATE54") (pin "A") (pinfunction "A_A") (pintype "input"))
      (node (ref "GATE57") (pin "A") (pinfunction "A_A") (pintype "input"))
    )
    (net (code "10") (name "1PPS_CLK{slash}") (class "Default")
      (node (ref "A_BUS") (pin "34") (pinfunction "34_34") (pintype "passive"))
      (node (ref "CON1") (pin "7") (pinfunction "7_7") (pintype "passive"))
      (node (ref "GATE1") (pin "A") (pinfunction "A_A") (pintype "input"))
    )
    (net (code "11") (name "AC_CLK{slash}") (class "Default")
      (node (ref "A_BUS") (pin "33") (pinfunction "33_33") (pintype "passive"))
      (node (ref "CON1") (pin "6") (pinfunction "6_6") (pintype "passive"))
      (node (ref "GATE110") (pin "B") (pinfunction "B_B") (pintype "input"))
      (node (ref "GATE141") (pin "B") (pinfunction "B_B") (pintype "input"))
      (node (ref "GATE159") (pin "B") (pinfunction "B_B") (pintype "input"))
      (node (ref "GATE29") (pin "B") (pinfunction "B_B") (pintype "input"))
      (node (ref "GATE54") (pin "B") (pinfunction "B_B") (pintype "input"))
      (node (ref "GATE85") (pin "B") (pinfunction "B_B") (pintype "input"))
    )
    (net (code "12") (name "HRS_SET_BTN") (class "Default")
      (node (ref "GATE114") (pin "B") (pinfunction "B_B") (pintype "input"))
      (node (ref "Q2") (pin "3") (pinfunction "D_3") (pintype "passive"))
      (node (ref "R6") (pin "1") (pinfunction "1_1") (pintype "passive"))
    )
    (net (code "13") (name "HRS_TENS_A") (class "Default")
      (node (ref "A_BUS") (pin "19") (pinfunction "19_19") (pintype "passive"))
      (node (ref "GATE150") (pin "Q") (pinfunction "Q_Q") (pintype "output"))
      (node (ref "GATE151") (pin "A") (pinfunction "A_A") (pintype "input"))
      (node (ref "GATE153") (pin "B") (pinfunction "B_B") (pintype "input"))
      (node (ref "GATE154") (pin "B") (pinfunction "B_B") (pintype "input"))
    )
    (net (code "14") (name "HRS_TENS_B") (class "Default")
      (node (ref "A_BUS") (pin "20") (pinfunction "20_20") (pintype "passive"))
      (node (ref "GATE156") (pin "Q") (pinfunction "Q_Q") (pintype "output"))
      (node (ref "GATE157") (pin "A") (pinfunction "A_A") (pintype "input"))
    )
    (net (code "15") (name "HRS_UNIT_A") (class "Default")
      (node (ref "A_BUS") (pin "15") (pinfunction "15_15") (pintype "passive"))
      (node (ref "GATE119") (pin "Q") (pinfunction "Q_Q") (pintype "output"))
      (node (ref "GATE120") (pin "A") (pinfunction "A_A") (pintype "input"))
      (node (ref "GATE122") (pin "B") (pinfunction "B_B") (pintype "input"))
      (node (ref "GATE123") (pin "B") (pinfunction "B_B") (pintype "input"))
    )
    (net (code "16") (name "HRS_UNIT_B") (class "Default")
      (node (ref "A_BUS") (pin "16") (pinfunction "16_16") (pintype "passive"))
      (node (ref "GATE125") (pin "Q") (pinfunction "Q_Q") (pintype "output"))
      (node (ref "GATE126") (pin "A") (pinfunction "A_A") (pintype "input"))
      (node (ref "GATE128") (pin "B") (pinfunction "B_B") (pintype "input"))
      (node (ref "GATE129") (pin "B") (pinfunction "B_B") (pintype "input"))
    )
    (net (code "17") (name "HRS_UNIT_C") (class "Default")
      (node (ref "A_BUS") (pin "17") (pinfunction "17_17") (pintype "passive"))
      (node (ref "GATE131") (pin "Q") (pinfunction "Q_Q") (pintype "output"))
      (node (ref "GATE132") (pin "A") (pinfunction "A_A") (pintype "input"))
      (node (ref "GATE134") (pin "B") (pinfunction "B_B") (pintype "input"))
      (node (ref "GATE135") (pin "B") (pinfunction "B_B") (pintype "input"))
    )
    (net (code "18") (name "HRS_UNIT_D") (class "Default")
      (node (ref "A_BUS") (pin "18") (pinfunction "18_18") (pintype "passive"))
      (node (ref "GATE137") (pin "Q") (pinfunction "Q_Q") (pintype "output"))
      (node (ref "GATE138") (pin "A") (pinfunction "A_A") (pintype "input"))
    )
    (net (code "19") (name "MCLR") (class "Default")
      (node (ref "A_BUS") (pin "35") (pinfunction "35_35") (pintype "passive"))
      (node (ref "CON1") (pin "5") (pinfunction "5_5") (pintype "passive"))
      (node (ref "GATE111") (pin "B") (pinfunction "B_B") (pintype "input"))
      (node (ref "GATE114") (pin "A") (pinfunction "A_A") (pintype "input"))
      (node (ref "GATE142") (pin "C") (pinfunction "C_C") (pintype "input"))
      (node (ref "GATE145") (pin "A") (pinfunction "A_A") (pintype "input"))
      (node (ref "GATE160") (pin "B") (pinfunction "B_B") (pintype "input"))
      (node (ref "GATE2") (pin "A") (pinfunction "A_A") (pintype "input"))
      (node (ref "GATE30") (pin "B") (pinfunction "B_B") (pintype "input"))
      (node (ref "GATE33") (pin "A") (pinfunction "A_A") (pintype "input"))
      (node (ref "GATE55") (pin "B") (pinfunction "B_B") (pintype "input"))
      (node (ref "GATE58") (pin "A") (pinfunction "A_A") (pintype "input"))
      (node (ref "GATE86") (pin "B") (pinfunction "B_B") (pintype "input"))
      (node (ref "GATE89") (pin "A") (pinfunction "A_A") (pintype "input"))
    )
    (net (code "20") (name "MIN_SET_BTN") (class "Default")
      (node (ref "GATE58") (pin "B") (pinfunction "B_B") (pintype "input"))
      (node (ref "Q1") (pin "3") (pinfunction "D_3") (pintype "passive"))
      (node (ref "R3") (pin "1") (pinfunction "1_1") (pintype "passive"))
    )
    (net (code "21") (name "MIN_TENS_A") (class "Default")
      (node (ref "A_BUS") (pin "12") (pinfunction "12_12") (pintype "passive"))
      (node (ref "GATE94") (pin "Q") (pinfunction "Q_Q") (pintype "output"))
      (node (ref "GATE95") (pin "A") (pinfunction "A_A") (pintype "input"))
      (node (ref "GATE97") (pin "B") (pinfunction "B_B") (pintype "input"))
      (node (ref "GATE98") (pin "B") (pinfunction "B_B") (pintype "input"))
    )
    (net (code "22") (name "MIN_TENS_B") (class "Default")
      (node (ref "A_BUS") (pin "13") (pinfunction "13_13") (pintype "passive"))
      (node (ref "GATE100") (pin "Q") (pinfunction "Q_Q") (pintype "output"))
      (node (ref "GATE101") (pin "A") (pinfunction "A_A") (pintype "input"))
      (node (ref "GATE103") (pin "B") (pinfunction "B_B") (pintype "input"))
      (node (ref "GATE104") (pin "B") (pinfunction "B_B") (pintype "input"))
    )
    (net (code "23") (name "MIN_TENS_C") (class "Default")
      (node (ref "A_BUS") (pin "14") (pinfunction "14_14") (pintype "passive"))
      (node (ref "GATE106") (pin "Q") (pinfunction "Q_Q") (pintype "output"))
      (node (ref "GATE107") (pin "A") (pinfunction "A_A") (pintype "input"))
    )
    (net (code "24") (name "MIN_UNIT_A") (class "Default")
      (node (ref "A_BUS") (pin "8") (pinfunction "8_8") (pintype "passive"))
      (node (ref "GATE63") (pin "Q") (pinfunction "Q_Q") (pintype "output"))
      (node (ref "GATE64") (pin "A") (pinfunction "A_A") (pintype "input"))
      (node (ref "GATE66") (pin "B") (pinfunction "B_B") (pintype "input"))
      (node (ref "GATE67") (pin "B") (pinfunction "B_B") (pintype "input"))
    )
    (net (code "25") (name "MIN_UNIT_B") (class "Default")
      (node (ref "A_BUS") (pin "9") (pinfunction "9_9") (pintype "passive"))
      (node (ref "GATE69") (pin "Q") (pinfunction "Q_Q") (pintype "output"))
      (node (ref "GATE70") (pin "A") (pinfunction "A_A") (pintype "input"))
      (node (ref "GATE72") (pin "B") (pinfunction "B_B") (pintype "input"))
      (node (ref "GATE73") (pin "B") (pinfunction "B_B") (pintype "input"))
    )
    (net (code "26") (name "MIN_UNIT_C") (class "Default")
      (node (ref "A_BUS") (pin "10") (pinfunction "10_10") (pintype "passive"))
      (node (ref "GATE75") (pin "Q") (pinfunction "Q_Q") (pintype "output"))
      (node (ref "GATE76") (pin "A") (pinfunction "A_A") (pintype "input"))
      (node (ref "GATE78") (pin "B") (pinfunction "B_B") (pintype "input"))
      (node (ref "GATE79") (pin "B") (pinfunction "B_B") (pintype "input"))
    )
    (net (code "27") (name "MIN_UNIT_D") (class "Default")
      (node (ref "A_BUS") (pin "11") (pinfunction "11_11") (pintype "passive"))
      (node (ref "GATE81") (pin "Q") (pinfunction "Q_Q") (pintype "output"))
      (node (ref "GATE82") (pin "A") (pinfunction "A_A") (pintype "input"))
    )
    (net (code "28") (name "Net-(GATE1-PadQ)") (class "Default")
      (node (ref "GATE1") (pin "Q") (pinfunction "Q_Q") (pintype "output"))
      (node (ref "GATE2") (pin "B") (pinfunction "B_B") (pintype "input"))
    )
    (net (code "29") (name "Net-(GATE2-PadQ)") (class "Default")
      (node (ref "GATE2") (pin "Q") (pinfunction "Q_Q") (pintype "output"))
      (node (ref "GATE4") (pin "B") (pinfunction "B_B") (pintype "input"))
      (node (ref "GATE5") (pin "B") (pinfunction "B_B") (pintype "input"))
    )
    (net (code "30") (name "Net-(GATE3-PadB)") (class "Default")
      (node (ref "GATE3") (pin "B") (pinfunction "B_B") (pintype "input"))
      (node (ref "GATE5") (pin "C") (pinfunction "C_C") (pintype "input"))
      (node (ref "GATE6") (pin "Q") (pinfunction "Q_Q") (pintype "output"))
    )
    (net (code "31") (name "Net-(GATE3-PadC)") (class "Default")
      (node (ref "GATE3") (pin "C") (pinfunction "C_C") (pintype "input"))
      (node (ref "GATE4") (pin "Q") (pinfunction "Q_Q") (pintype "output"))
      (node (ref "GATE5") (pin "A") (pinfunction "A_A") (pintype "input"))
      (node (ref "GATE7") (pin "A") (pinfunction "A_A") (pintype "input"))
    )
    (net (code "32") (name "Net-(GATE3-PadQ)") (class "Default")
      (node (ref "GATE3") (pin "Q") (pinfunction "Q_Q") (pintype "output"))
      (node (ref "GATE4") (pin "A") (pinfunction "A_A") (pintype "input"))
    )
    (net (code "33") (name "Net-(GATE5-PadQ)") (class "Default")
      (node (ref "GATE5") (pin "Q") (pinfunction "Q_Q") (pintype "output"))
      (node (ref "GATE6") (pin "A") (pinfunction "A_A") (pintype "input"))
      (node (ref "GATE8") (pin "B") (pinfunction "B_B") (pintype "input"))
    )
    (net (code "34") (name "Net-(GATE6-PadB)") (class "Default")
      (node (ref "GATE6") (pin "B") (pinfunction "B_B") (pintype "input"))
      (node (ref "GATE7") (pin "B") (pinfunction "B_B") (pintype "input"))
      (node (ref "GATE8") (pin "Q") (pinfunction "Q_Q") (pintype "output"))
    )
    (net (code "35") (name "Net-(GATE10-PadA)") (class "Default")
      (node (ref "GATE10") (pin "A") (pinfunction "A_A") (pintype "input"))
      (node (ref "GATE9") (pin "Q") (pinfunction "Q_Q") (pintype "output"))
    )
    (net (code "36") (name "Net-(GATE10-PadQ)") (class "Default")
      (node (ref "GATE10") (pin "Q") (pinfunction "Q_Q") (pintype "output"))
      (node (ref "GATE11") (pin "A") (pinfunction "A_A") (pintype "input"))
      (node (ref "GATE13") (pin "A") (pinfunction "A_A") (pintype "input"))
      (node (ref "GATE9") (pin "C") (pinfunction "C_C") (pintype "input"))
    )
    (net (code "37") (name "Net-(GATE11-PadC)") (class "Default")
      (node (ref "GATE11") (pin "C") (pinfunction "C_C") (pintype "input"))
      (node (ref "GATE12") (pin "Q") (pinfunction "Q_Q") (pintype "output"))
      (node (ref "GATE9") (pin "B") (pinfunction "B_B") (pintype "input"))
    )
    (net (code "38") (name "Net-(GATE11-PadQ)") (class "Default")
      (node (ref "GATE11") (pin "Q") (pinfunction "Q_Q") (pintype "output"))
      (node (ref "GATE12") (pin "A") (pinfunction "A_A") (pintype "input"))
      (node (ref "GATE14") (pin "B") (pinfunction "B_B") (pintype "input"))
    )
    (net (code "39") (name "Net-(GATE12-PadB)") (class "Default")
      (node (ref "GATE12") (pin "B") (pinfunction "B_B") (pintype "input"))
      (node (ref "GATE13") (pin "B") (pinfunction "B_B") (pintype "input"))
      (node (ref "GATE14") (pin "Q") (pinfunction "Q_Q") (pintype "output"))
      (node (ref "GATE27") (pin "B") (pinfunction "B_B") (pintype "input"))
    )
    (net (code "40") (name "Net-(GATE15-PadB)") (class "Default")
      (node (ref "GATE15") (pin "B") (pinfunction "B_B") (pintype "input"))
      (node (ref "GATE17") (pin "C") (pinfunction "C_C") (pintype "input"))
      (node (ref "GATE18") (pin "Q") (pinfunction "Q_Q") (pintype "output"))
    )
    (net (code "41") (name "Net-(GATE15-PadC)") (class "Default")
      (node (ref "GATE15") (pin "C") (pinfunction "C_C") (pintype "input"))
      (node (ref "GATE16") (pin "Q") (pinfunction "Q_Q") (pintype "output"))
      (node (ref "GATE17") (pin "A") (pinfunction "A_A") (pintype "input"))
      (node (ref "GATE19") (pin "A") (pinfunction "A_A") (pintype "input"))
    )
    (net (code "42") (name "Net-(GATE15-PadQ)") (class "Default")
      (node (ref "GATE15") (pin "Q") (pinfunction "Q_Q") (pintype "output"))
      (node (ref "GATE16") (pin "A") (pinfunction "A_A") (pintype "input"))
    )
    (net (code "43") (name "Net-(GATE17-PadQ)") (class "Default")
      (node (ref "GATE17") (pin "Q") (pinfunction "Q_Q") (pintype "output"))
      (node (ref "GATE18") (pin "A") (pinfunction "A_A") (pintype "input"))
      (node (ref "GATE20") (pin "B") (pinfunction "B_B") (pintype "input"))
    )
    (net (code "44") (name "Net-(GATE18-PadB)") (class "Default")
      (node (ref "GATE18") (pin "B") (pinfunction "B_B") (pintype "input"))
      (node (ref "GATE19") (pin "B") (pinfunction "B_B") (pintype "input"))
      (node (ref "GATE20") (pin "Q") (pinfunction "Q_Q") (pintype "output"))
    )
    (net (code "45") (name "Net-(GATE21-PadB)") (class "Default")
      (node (ref "GATE21") (pin "B") (pinfunction "B_B") (pintype "input"))
      (node (ref "GATE23") (pin "C") (pinfunction "C_C") (pintype "input"))
      (node (ref "GATE24") (pin "Q") (pinfunction "Q_Q") (pintype "output"))
    )
    (net (code "46") (name "Net-(GATE21-PadC)") (class "Default")
      (node (ref "GATE21") (pin "C") (pinfunction "C_C") (pintype "input"))
      (node (ref "GATE22") (pin "Q") (pinfunction "Q_Q") (pintype "output"))
      (node (ref "GATE23") (pin "A") (pinfunction "A_A") (pintype "input"))
      (node (ref "GATE25") (pin "A") (pinfunction "A_A") (pintype "input"))
    )
    (net (code "47") (name "Net-(GATE21-PadQ)") (class "Default")
      (node (ref "GATE21") (pin "Q") (pinfunction "Q_Q") (pintype "output"))
      (node (ref "GATE22") (pin "A") (pinfunction "A_A") (pintype "input"))
    )
    (net (code "48") (name "Net-(GATE23-PadQ)") (class "Default")
      (node (ref "GATE23") (pin "Q") (pinfunction "Q_Q") (pintype "output"))
      (node (ref "GATE24") (pin "A") (pinfunction "A_A") (pintype "input"))
      (node (ref "GATE26") (pin "B") (pinfunction "B_B") (pintype "input"))
    )
    (net (code "49") (name "Net-(GATE24-PadB)") (class "Default")
      (node (ref "GATE24") (pin "B") (pinfunction "B_B") (pintype "input"))
      (node (ref "GATE25") (pin "B") (pinfunction "B_B") (pintype "input"))
      (node (ref "GATE26") (pin "Q") (pinfunction "Q_Q") (pintype "output"))
      (node (ref "GATE27") (pin "A") (pinfunction "A_A") (pintype "input"))
    )
    (net (code "50") (name "Net-(GATE27-PadQ)") (class "Default")
      (node (ref "GATE27") (pin "Q") (pinfunction "Q_Q") (pintype "output"))
      (node (ref "GATE28") (pin "A") (pinfunction "A_A") (pintype "input"))
    )
    (net (code "51") (name "Net-(GATE28-PadB)") (class "Default")
      (node (ref "GATE28") (pin "B") (pinfunction "B_B") (pintype "input"))
      (node (ref "GATE29") (pin "Q") (pinfunction "Q_Q") (pintype "output"))
      (node (ref "GATE30") (pin "A") (pinfunction "A_A") (pintype "input"))
    )
    (net (code "52") (name "Net-(GATE28-PadQ)") (class "Default")
      (node (ref "GATE28") (pin "Q") (pinfunction "Q_Q") (pintype "output"))
      (node (ref "GATE29") (pin "A") (pinfunction "A_A") (pintype "input"))
      (node (ref "GATE32") (pin "A") (pinfunction "A_A") (pintype "input"))
    )
    (net (code "53") (name "Net-(GATE30-PadQ)") (class "Default")
      (node (ref "GATE30") (pin "Q") (pinfunction "Q_Q") (pintype "output"))
      (node (ref "GATE31") (pin "A") (pinfunction "A_A") (pintype "input"))
    )
    (net (code "54") (name "Net-(GATE32-PadQ)") (class "Default")
      (node (ref "GATE32") (pin "Q") (pinfunction "Q_Q") (pintype "output"))
      (node (ref "GATE33") (pin "B") (pinfunction "B_B") (pintype "input"))
    )
    (net (code "55") (name "Net-(GATE33-PadQ)") (class "Default")
      (node (ref "GATE33") (pin "Q") (pinfunction "Q_Q") (pintype "output"))
      (node (ref "GATE35") (pin "B") (pinfunction "B_B") (pintype "input"))
      (node (ref "GATE36") (pin "B") (pinfunction "B_B") (pintype "input"))
    )
    (net (code "56") (name "Net-(GATE34-PadB)") (class "Default")
      (node (ref "GATE34") (pin "B") (pinfunction "B_B") (pintype "input"))
      (node (ref "GATE36") (pin "C") (pinfunction "C_C") (pintype "input"))
      (node (ref "GATE37") (pin "Q") (pinfunction "Q_Q") (pintype "output"))
    )
    (net (code "57") (name "Net-(GATE34-PadC)") (class "Default")
      (node (ref "GATE34") (pin "C") (pinfunction "C_C") (pintype "input"))
      (node (ref "GATE35") (pin "Q") (pinfunction "Q_Q") (pintype "output"))
      (node (ref "GATE36") (pin "A") (pinfunction "A_A") (pintype "input"))
      (node (ref "GATE38") (pin "A") (pinfunction "A_A") (pintype "input"))
    )
    (net (code "58") (name "Net-(GATE34-PadQ)") (class "Default")
      (node (ref "GATE34") (pin "Q") (pinfunction "Q_Q") (pintype "output"))
      (node (ref "GATE35") (pin "A") (pinfunction "A_A") (pintype "input"))
    )
    (net (code "59") (name "Net-(GATE36-PadQ)") (class "Default")
      (node (ref "GATE36") (pin "Q") (pinfunction "Q_Q") (pintype "output"))
      (node (ref "GATE37") (pin "A") (pinfunction "A_A") (pintype "input"))
      (node (ref "GATE39") (pin "B") (pinfunction "B_B") (pintype "input"))
    )
    (net (code "60") (name "Net-(GATE37-PadB)") (class "Default")
      (node (ref "GATE37") (pin "B") (pinfunction "B_B") (pintype "input"))
      (node (ref "GATE38") (pin "B") (pinfunction "B_B") (pintype "input"))
      (node (ref "GATE39") (pin "Q") (pinfunction "Q_Q") (pintype "output"))
    )
    (net (code "61") (name "Net-(GATE40-PadB)") (class "Default")
      (node (ref "GATE40") (pin "B") (pinfunction "B_B") (pintype "input"))
      (node (ref "GATE42") (pin "C") (pinfunction "C_C") (pintype "input"))
      (node (ref "GATE43") (pin "Q") (pinfunction "Q_Q") (pintype "output"))
    )
    (net (code "62") (name "Net-(GATE40-PadC)") (class "Default")
      (node (ref "GATE40") (pin "C") (pinfunction "C_C") (pintype "input"))
      (node (ref "GATE41") (pin "Q") (pinfunction "Q_Q") (pintype "output"))
      (node (ref "GATE42") (pin "A") (pinfunction "A_A") (pintype "input"))
      (node (ref "GATE44") (pin "A") (pinfunction "A_A") (pintype "input"))
    )
    (net (code "63") (name "Net-(GATE40-PadQ)") (class "Default")
      (node (ref "GATE40") (pin "Q") (pinfunction "Q_Q") (pintype "output"))
      (node (ref "GATE41") (pin "A") (pinfunction "A_A") (pintype "input"))
    )
    (net (code "64") (name "Net-(GATE42-PadQ)") (class "Default")
      (node (ref "GATE42") (pin "Q") (pinfunction "Q_Q") (pintype "output"))
      (node (ref "GATE43") (pin "A") (pinfunction "A_A") (pintype "input"))
      (node (ref "GATE45") (pin "B") (pinfunction "B_B") (pintype "input"))
    )
    (net (code "65") (name "Net-(GATE43-PadB)") (class "Default")
      (node (ref "GATE43") (pin "B") (pinfunction "B_B") (pintype "input"))
      (node (ref "GATE44") (pin "B") (pinfunction "B_B") (pintype "input"))
      (node (ref "GATE45") (pin "Q") (pinfunction "Q_Q") (pintype "output"))
      (node (ref "GATE52") (pin "B") (pinfunction "B_B") (pintype "input"))
    )
    (net (code "66") (name "Net-(GATE46-PadB)") (class "Default")
      (node (ref "GATE46") (pin "B") (pinfunction "B_B") (pintype "input"))
      (node (ref "GATE48") (pin "C") (pinfunction "C_C") (pintype "input"))
      (node (ref "GATE49") (pin "Q") (pinfunction "Q_Q") (pintype "output"))
    )
    (net (code "67") (name "Net-(GATE46-PadC)") (class "Default")
      (node (ref "GATE46") (pin "C") (pinfunction "C_C") (pintype "input"))
      (node (ref "GATE47") (pin "Q") (pinfunction "Q_Q") (pintype "output"))
      (node (ref "GATE48") (pin "A") (pinfunction "A_A") (pintype "input"))
      (node (ref "GATE50") (pin "A") (pinfunction "A_A") (pintype "input"))
    )
    (net (code "68") (name "Net-(GATE46-PadQ)") (class "Default")
      (node (ref "GATE46") (pin "Q") (pinfunction "Q_Q") (pintype "output"))
      (node (ref "GATE47") (pin "A") (pinfunction "A_A") (pintype "input"))
    )
    (net (code "69") (name "Net-(GATE48-PadQ)") (class "Default")
      (node (ref "GATE48") (pin "Q") (pinfunction "Q_Q") (pintype "output"))
      (node (ref "GATE49") (pin "A") (pinfunction "A_A") (pintype "input"))
      (node (ref "GATE51") (pin "B") (pinfunction "B_B") (pintype "input"))
    )
    (net (code "70") (name "Net-(GATE49-PadB)") (class "Default")
      (node (ref "GATE49") (pin "B") (pinfunction "B_B") (pintype "input"))
      (node (ref "GATE50") (pin "B") (pinfunction "B_B") (pintype "input"))
      (node (ref "GATE51") (pin "Q") (pinfunction "Q_Q") (pintype "output"))
      (node (ref "GATE52") (pin "A") (pinfunction "A_A") (pintype "input"))
    )
    (net (code "71") (name "Net-(GATE52-PadQ)") (class "Default")
      (node (ref "GATE52") (pin "Q") (pinfunction "Q_Q") (pintype "output"))
      (node (ref "GATE53") (pin "A") (pinfunction "A_A") (pintype "input"))
    )
    (net (code "72") (name "Net-(GATE53-PadB)") (class "Default")
      (node (ref "GATE53") (pin "B") (pinfunction "B_B") (pintype "input"))
      (node (ref "GATE54") (pin "Q") (pinfunction "Q_Q") (pintype "output"))
      (node (ref "GATE55") (pin "A") (pinfunction "A_A") (pintype "input"))
    )
    (net (code "73") (name "Net-(GATE55-PadQ)") (class "Default")
      (node (ref "GATE55") (pin "Q") (pinfunction "Q_Q") (pintype "output"))
      (node (ref "GATE56") (pin "A") (pinfunction "A_A") (pintype "input"))
    )
    (net (code "74") (name "Net-(GATE57-PadQ)") (class "Default")
      (node (ref "GATE57") (pin "Q") (pinfunction "Q_Q") (pintype "output"))
      (node (ref "GATE58") (pin "C") (pinfunction "C_C") (pintype "input"))
    )
    (net (code "75") (name "Net-(GATE58-PadQ)") (class "Default")
      (node (ref "GATE58") (pin "Q") (pinfunction "Q_Q") (pintype "output"))
      (node (ref "GATE60") (pin "B") (pinfunction "B_B") (pintype "input"))
      (node (ref "GATE61") (pin "B") (pinfunction "B_B") (pintype "input"))
    )
    (net (code "76") (name "Net-(GATE59-PadB)") (class "Default")
      (node (ref "GATE59") (pin "B") (pinfunction "B_B") (pintype "input"))
      (node (ref "GATE61") (pin "C") (pinfunction "C_C") (pintype "input"))
      (node (ref "GATE62") (pin "Q") (pinfunction "Q_Q") (pintype "output"))
    )
    (net (code "77") (name "Net-(GATE59-PadC)") (class "Default")
      (node (ref "GATE59") (pin "C") (pinfunction "C_C") (pintype "input"))
      (node (ref "GATE60") (pin "Q") (pinfunction "Q_Q") (pintype "output"))
      (node (ref "GATE61") (pin "A") (pinfunction "A_A") (pintype "input"))
      (node (ref "GATE63") (pin "A") (pinfunction "A_A") (pintype "input"))
    )
    (net (code "78") (name "Net-(GATE59-PadQ)") (class "Default")
      (node (ref "GATE59") (pin "Q") (pinfunction "Q_Q") (pintype "output"))
      (node (ref "GATE60") (pin "A") (pinfunction "A_A") (pintype "input"))
    )
    (net (code "79") (name "Net-(GATE61-PadQ)") (class "Default")
      (node (ref "GATE61") (pin "Q") (pinfunction "Q_Q") (pintype "output"))
      (node (ref "GATE62") (pin "A") (pinfunction "A_A") (pintype "input"))
      (node (ref "GATE64") (pin "B") (pinfunction "B_B") (pintype "input"))
    )
    (net (code "80") (name "Net-(GATE62-PadB)") (class "Default")
      (node (ref "GATE62") (pin "B") (pinfunction "B_B") (pintype "input"))
      (node (ref "GATE63") (pin "B") (pinfunction "B_B") (pintype "input"))
      (node (ref "GATE64") (pin "Q") (pinfunction "Q_Q") (pintype "output"))
    )
    (net (code "81") (name "Net-(GATE65-PadB)") (class "Default")
      (node (ref "GATE65") (pin "B") (pinfunction "B_B") (pintype "input"))
      (node (ref "GATE67") (pin "C") (pinfunction "C_C") (pintype "input"))
      (node (ref "GATE68") (pin "Q") (pinfunction "Q_Q") (pintype "output"))
    )
    (net (code "82") (name "Net-(GATE65-PadC)") (class "Default")
      (node (ref "GATE65") (pin "C") (pinfunction "C_C") (pintype "input"))
      (node (ref "GATE66") (pin "Q") (pinfunction "Q_Q") (pintype "output"))
      (node (ref "GATE67") (pin "A") (pinfunction "A_A") (pintype "input"))
      (node (ref "GATE69") (pin "A") (pinfunction "A_A") (pintype "input"))
    )
    (net (code "83") (name "Net-(GATE65-PadQ)") (class "Default")
      (node (ref "GATE65") (pin "Q") (pinfunction "Q_Q") (pintype "output"))
      (node (ref "GATE66") (pin "A") (pinfunction "A_A") (pintype "input"))
    )
    (net (code "84") (name "Net-(GATE67-PadQ)") (class "Default")
      (node (ref "GATE67") (pin "Q") (pinfunction "Q_Q") (pintype "output"))
      (node (ref "GATE68") (pin "A") (pinfunction "A_A") (pintype "input"))
      (node (ref "GATE70") (pin "B") (pinfunction "B_B") (pintype "input"))
    )
    (net (code "85") (name "Net-(GATE68-PadB)") (class "Default")
      (node (ref "GATE68") (pin "B") (pinfunction "B_B") (pintype "input"))
      (node (ref "GATE69") (pin "B") (pinfunction "B_B") (pintype "input"))
      (node (ref "GATE70") (pin "Q") (pinfunction "Q_Q") (pintype "output"))
      (node (ref "GATE83") (pin "B") (pinfunction "B_B") (pintype "input"))
    )
    (net (code "86") (name "Net-(GATE71-PadB)") (class "Default")
      (node (ref "GATE71") (pin "B") (pinfunction "B_B") (pintype "input"))
      (node (ref "GATE73") (pin "C") (pinfunction "C_C") (pintype "input"))
      (node (ref "GATE74") (pin "Q") (pinfunction "Q_Q") (pintype "output"))
    )
    (net (code "87") (name "Net-(GATE71-PadC)") (class "Default")
      (node (ref "GATE71") (pin "C") (pinfunction "C_C") (pintype "input"))
      (node (ref "GATE72") (pin "Q") (pinfunction "Q_Q") (pintype "output"))
      (node (ref "GATE73") (pin "A") (pinfunction "A_A") (pintype "input"))
      (node (ref "GATE75") (pin "A") (pinfunction "A_A") (pintype "input"))
    )
    (net (code "88") (name "Net-(GATE71-PadQ)") (class "Default")
      (node (ref "GATE71") (pin "Q") (pinfunction "Q_Q") (pintype "output"))
      (node (ref "GATE72") (pin "A") (pinfunction "A_A") (pintype "input"))
    )
    (net (code "89") (name "Net-(GATE73-PadQ)") (class "Default")
      (node (ref "GATE73") (pin "Q") (pinfunction "Q_Q") (pintype "output"))
      (node (ref "GATE74") (pin "A") (pinfunction "A_A") (pintype "input"))
      (node (ref "GATE76") (pin "B") (pinfunction "B_B") (pintype "input"))
    )
    (net (code "90") (name "Net-(GATE74-PadB)") (class "Default")
      (node (ref "GATE74") (pin "B") (pinfunction "B_B") (pintype "input"))
      (node (ref "GATE75") (pin "B") (pinfunction "B_B") (pintype "input"))
      (node (ref "GATE76") (pin "Q") (pinfunction "Q_Q") (pintype "output"))
    )
    (net (code "91") (name "Net-(GATE77-PadB)") (class "Default")
      (node (ref "GATE77") (pin "B") (pinfunction "B_B") (pintype "input"))
      (node (ref "GATE79") (pin "C") (pinfunction "C_C") (pintype "input"))
      (node (ref "GATE80") (pin "Q") (pinfunction "Q_Q") (pintype "output"))
    )
    (net (code "92") (name "Net-(GATE77-PadC)") (class "Default")
      (node (ref "GATE77") (pin "C") (pinfunction "C_C") (pintype "input"))
      (node (ref "GATE78") (pin "Q") (pinfunction "Q_Q") (pintype "output"))
      (node (ref "GATE79") (pin "A") (pinfunction "A_A") (pintype "input"))
      (node (ref "GATE81") (pin "A") (pinfunction "A_A") (pintype "input"))
    )
    (net (code "93") (name "Net-(GATE77-PadQ)") (class "Default")
      (node (ref "GATE77") (pin "Q") (pinfunction "Q_Q") (pintype "output"))
      (node (ref "GATE78") (pin "A") (pinfunction "A_A") (pintype "input"))
    )
    (net (code "94") (name "Net-(GATE79-PadQ)") (class "Default")
      (node (ref "GATE79") (pin "Q") (pinfunction "Q_Q") (pintype "output"))
      (node (ref "GATE80") (pin "A") (pinfunction "A_A") (pintype "input"))
      (node (ref "GATE82") (pin "B") (pinfunction "B_B") (pintype "input"))
    )
    (net (code "95") (name "Net-(GATE80-PadB)") (class "Default")
      (node (ref "GATE80") (pin "B") (pinfunction "B_B") (pintype "input"))
      (node (ref "GATE81") (pin "B") (pinfunction "B_B") (pintype "input"))
      (node (ref "GATE82") (pin "Q") (pinfunction "Q_Q") (pintype "output"))
      (node (ref "GATE83") (pin "A") (pinfunction "A_A") (pintype "input"))
    )
    (net (code "96") (name "Net-(GATE83-PadQ)") (class "Default")
      (node (ref "GATE83") (pin "Q") (pinfunction "Q_Q") (pintype "output"))
      (node (ref "GATE84") (pin "A") (pinfunction "A_A") (pintype "input"))
    )
    (net (code "97") (name "Net-(GATE84-PadB)") (class "Default")
      (node (ref "GATE84") (pin "B") (pinfunction "B_B") (pintype "input"))
      (node (ref "GATE85") (pin "Q") (pinfunction "Q_Q") (pintype "output"))
      (node (ref "GATE86") (pin "A") (pinfunction "A_A") (pintype "input"))
    )
    (net (code "98") (name "Net-(GATE84-PadQ)") (class "Default")
      (node (ref "GATE84") (pin "Q") (pinfunction "Q_Q") (pintype "output"))
      (node (ref "GATE85") (pin "A") (pinfunction "A_A") (pintype "input"))
      (node (ref "GATE88") (pin "A") (pinfunction "A_A") (pintype "input"))
    )
    (net (code "99") (name "Net-(GATE86-PadQ)") (class "Default")
      (node (ref "GATE86") (pin "Q") (pinfunction "Q_Q") (pintype "output"))
      (node (ref "GATE87") (pin "A") (pinfunction "A_A") (pintype "input"))
    )
    (net (code "100") (name "Net-(GATE88-PadQ)") (class "Default")
      (node (ref "GATE88") (pin "Q") (pinfunction "Q_Q") (pintype "output"))
      (node (ref "GATE89") (pin "B") (pinfunction "B_B") (pintype "input"))
    )
    (net (code "101") (name "Net-(GATE89-PadQ)") (class "Default")
      (node (ref "GATE89") (pin "Q") (pinfunction "Q_Q") (pintype "output"))
      (node (ref "GATE91") (pin "B") (pinfunction "B_B") (pintype "input"))
      (node (ref "GATE92") (pin "B") (pinfunction "B_B") (pintype "input"))
    )
    (net (code "102") (name "Net-(GATE90-PadB)") (class "Default")
      (node (ref "GATE90") (pin "B") (pinfunction "B_B") (pintype "input"))
      (node (ref "GATE92") (pin "C") (pinfunction "C_C") (pintype "input"))
      (node (ref "GATE93") (pin "Q") (pinfunction "Q_Q") (pintype "output"))
    )
    (net (code "103") (name "Net-(GATE90-PadC)") (class "Default")
      (node (ref "GATE90") (pin "C") (pinfunction "C_C") (pintype "input"))
      (node (ref "GATE91") (pin "Q") (pinfunction "Q_Q") (pintype "output"))
      (node (ref "GATE92") (pin "A") (pinfunction "A_A") (pintype "input"))
      (node (ref "GATE94") (pin "A") (pinfunction "A_A") (pintype "input"))
    )
    (net (code "104") (name "Net-(GATE90-PadQ)") (class "Default")
      (node (ref "GATE90") (pin "Q") (pinfunction "Q_Q") (pintype "output"))
      (node (ref "GATE91") (pin "A") (pinfunction "A_A") (pintype "input"))
    )
    (net (code "105") (name "Net-(GATE92-PadQ)") (class "Default")
      (node (ref "GATE92") (pin "Q") (pinfunction "Q_Q") (pintype "output"))
      (node (ref "GATE93") (pin "A") (pinfunction "A_A") (pintype "input"))
      (node (ref "GATE95") (pin "B") (pinfunction "B_B") (pintype "input"))
    )
    (net (code "106") (name "Net-(GATE93-PadB)") (class "Default")
      (node (ref "GATE93") (pin "B") (pinfunction "B_B") (pintype "input"))
      (node (ref "GATE94") (pin "B") (pinfunction "B_B") (pintype "input"))
      (node (ref "GATE95") (pin "Q") (pinfunction "Q_Q") (pintype "output"))
    )
    (net (code "107") (name "Net-(GATE96-PadB)") (class "Default")
      (node (ref "GATE96") (pin "B") (pinfunction "B_B") (pintype "input"))
      (node (ref "GATE98") (pin "C") (pinfunction "C_C") (pintype "input"))
      (node (ref "GATE99") (pin "Q") (pinfunction "Q_Q") (pintype "output"))
    )
    (net (code "108") (name "Net-(GATE96-PadQ)") (class "Default")
      (node (ref "GATE96") (pin "Q") (pinfunction "Q_Q") (pintype "output"))
      (node (ref "GATE97") (pin "A") (pinfunction "A_A") (pintype "input"))
    )
    (net (code "109") (name "Net-(GATE100-PadA)") (class "Default")
      (node (ref "GATE100") (pin "A") (pinfunction "A_A") (pintype "input"))
      (node (ref "GATE96") (pin "C") (pinfunction "C_C") (pintype "input"))
      (node (ref "GATE97") (pin "Q") (pinfunction "Q_Q") (pintype "output"))
      (node (ref "GATE98") (pin "A") (pinfunction "A_A") (pintype "input"))
    )
    (net (code "110") (name "Net-(GATE100-PadB)") (class "Default")
      (node (ref "GATE100") (pin "B") (pinfunction "B_B") (pintype "input"))
      (node (ref "GATE101") (pin "Q") (pinfunction "Q_Q") (pintype "output"))
      (node (ref "GATE108") (pin "B") (pinfunction "B_B") (pintype "input"))
      (node (ref "GATE99") (pin "B") (pinfunction "B_B") (pintype "input"))
    )
    (net (code "111") (name "Net-(GATE101-PadB)") (class "Default")
      (node (ref "GATE101") (pin "B") (pinfunction "B_B") (pintype "input"))
      (node (ref "GATE98") (pin "Q") (pinfunction "Q_Q") (pintype "output"))
      (node (ref "GATE99") (pin "A") (pinfunction "A_A") (pintype "input"))
    )
    (net (code "112") (name "Net-(GATE102-PadB)") (class "Default")
      (node (ref "GATE102") (pin "B") (pinfunction "B_B") (pintype "input"))
      (node (ref "GATE104") (pin "C") (pinfunction "C_C") (pintype "input"))
      (node (ref "GATE105") (pin "Q") (pinfunction "Q_Q") (pintype "output"))
    )
    (net (code "113") (name "Net-(GATE102-PadC)") (class "Default")
      (node (ref "GATE102") (pin "C") (pinfunction "C_C") (pintype "input"))
      (node (ref "GATE103") (pin "Q") (pinfunction "Q_Q") (pintype "output"))
      (node (ref "GATE104") (pin "A") (pinfunction "A_A") (pintype "input"))
      (node (ref "GATE106") (pin "A") (pinfunction "A_A") (pintype "input"))
    )
    (net (code "114") (name "Net-(GATE102-PadQ)") (class "Default")
      (node (ref "GATE102") (pin "Q") (pinfunction "Q_Q") (pintype "output"))
      (node (ref "GATE103") (pin "A") (pinfunction "A_A") (pintype "input"))
    )
    (net (code "115") (name "Net-(GATE104-PadQ)") (class "Default")
      (node (ref "GATE104") (pin "Q") (pinfunction "Q_Q") (pintype "output"))
      (node (ref "GATE105") (pin "A") (pinfunction "A_A") (pintype "input"))
      (node (ref "GATE107") (pin "B") (pinfunction "B_B") (pintype "input"))
    )
    (net (code "116") (name "Net-(GATE105-PadB)") (class "Default")
      (node (ref "GATE105") (pin "B") (pinfunction "B_B") (pintype "input"))
      (node (ref "GATE106") (pin "B") (pinfunction "B_B") (pintype "input"))
      (node (ref "GATE107") (pin "Q") (pinfunction "Q_Q") (pintype "output"))
      (node (ref "GATE108") (pin "A") (pinfunction "A_A") (pintype "input"))
    )
    (net (code "117") (name "Net-(GATE108-PadQ)") (class "Default")
      (node (ref "GATE108") (pin "Q") (pinfunction "Q_Q") (pintype "output"))
      (node (ref "GATE109") (pin "A") (pinfunction "A_A") (pintype "input"))
    )
    (net (code "118") (name "Net-(GATE109-PadB)") (class "Default")
      (node (ref "GATE109") (pin "B") (pinfunction "B_B") (pintype "input"))
      (node (ref "GATE110") (pin "Q") (pinfunction "Q_Q") (pintype "output"))
      (node (ref "GATE111") (pin "A") (pinfunction "A_A") (pintype "input"))
    )
    (net (code "119") (name "Net-(GATE111-PadQ)") (class "Default")
      (node (ref "GATE111") (pin "Q") (pinfunction "Q_Q") (pintype "output"))
      (node (ref "GATE112") (pin "A") (pinfunction "A_A") (pintype "input"))
    )
    (net (code "120") (name "Net-(GATE113-PadQ)") (class "Default")
      (node (ref "GATE113") (pin "Q") (pinfunction "Q_Q") (pintype "output"))
      (node (ref "GATE114") (pin "C") (pinfunction "C_C") (pintype "input"))
    )
    (net (code "121") (name "Net-(GATE114-PadQ)") (class "Default")
      (node (ref "GATE114") (pin "Q") (pinfunction "Q_Q") (pintype "output"))
      (node (ref "GATE116") (pin "B") (pinfunction "B_B") (pintype "input"))
      (node (ref "GATE117") (pin "B") (pinfunction "B_B") (pintype "input"))
    )
    (net (code "122") (name "Net-(GATE115-PadB)") (class "Default")
      (node (ref "GATE115") (pin "B") (pinfunction "B_B") (pintype "input"))
      (node (ref "GATE117") (pin "C") (pinfunction "C_C") (pintype "input"))
      (node (ref "GATE118") (pin "Q") (pinfunction "Q_Q") (pintype "output"))
    )
    (net (code "123") (name "Net-(GATE115-PadC)") (class "Default")
      (node (ref "GATE115") (pin "C") (pinfunction "C_C") (pintype "input"))
      (node (ref "GATE116") (pin "Q") (pinfunction "Q_Q") (pintype "output"))
      (node (ref "GATE117") (pin "A") (pinfunction "A_A") (pintype "input"))
      (node (ref "GATE119") (pin "A") (pinfunction "A_A") (pintype "input"))
    )
    (net (code "124") (name "Net-(GATE115-PadQ)") (class "Default")
      (node (ref "GATE115") (pin "Q") (pinfunction "Q_Q") (pintype "output"))
      (node (ref "GATE116") (pin "A") (pinfunction "A_A") (pintype "input"))
    )
    (net (code "125") (name "Net-(GATE117-PadQ)") (class "Default")
      (node (ref "GATE117") (pin "Q") (pinfunction "Q_Q") (pintype "output"))
      (node (ref "GATE118") (pin "A") (pinfunction "A_A") (pintype "input"))
      (node (ref "GATE120") (pin "B") (pinfunction "B_B") (pintype "input"))
    )
    (net (code "126") (name "Net-(GATE118-PadB)") (class "Default")
      (node (ref "GATE118") (pin "B") (pinfunction "B_B") (pintype "input"))
      (node (ref "GATE119") (pin "B") (pinfunction "B_B") (pintype "input"))
      (node (ref "GATE120") (pin "Q") (pinfunction "Q_Q") (pintype "output"))
    )
    (net (code "127") (name "Net-(GATE121-PadB)") (class "Default")
      (node (ref "GATE121") (pin "B") (pinfunction "B_B") (pintype "input"))
      (node (ref "GATE123") (pin "C") (pinfunction "C_C") (pintype "input"))
      (node (ref "GATE124") (pin "Q") (pinfunction "Q_Q") (pintype "output"))
    )
    (net (code "128") (name "Net-(GATE121-PadC)") (class "Default")
      (node (ref "GATE121") (pin "C") (pinfunction "C_C") (pintype "input"))
      (node (ref "GATE122") (pin "Q") (pinfunction "Q_Q") (pintype "output"))
      (node (ref "GATE123") (pin "A") (pinfunction "A_A") (pintype "input"))
      (node (ref "GATE125") (pin "A") (pinfunction "A_A") (pintype "input"))
    )
    (net (code "129") (name "Net-(GATE121-PadQ)") (class "Default")
      (node (ref "GATE121") (pin "Q") (pinfunction "Q_Q") (pintype "output"))
      (node (ref "GATE122") (pin "A") (pinfunction "A_A") (pintype "input"))
    )
    (net (code "130") (name "Net-(GATE123-PadQ)") (class "Default")
      (node (ref "GATE123") (pin "Q") (pinfunction "Q_Q") (pintype "output"))
      (node (ref "GATE124") (pin "A") (pinfunction "A_A") (pintype "input"))
      (node (ref "GATE126") (pin "B") (pinfunction "B_B") (pintype "input"))
    )
    (net (code "131") (name "Net-(GATE124-PadB)") (class "Default")
      (node (ref "GATE124") (pin "B") (pinfunction "B_B") (pintype "input"))
      (node (ref "GATE125") (pin "B") (pinfunction "B_B") (pintype "input"))
      (node (ref "GATE126") (pin "Q") (pinfunction "Q_Q") (pintype "output"))
      (node (ref "GATE139") (pin "B") (pinfunction "B_B") (pintype "input"))
    )
    (net (code "132") (name "Net-(GATE127-PadB)") (class "Default")
      (node (ref "GATE127") (pin "B") (pinfunction "B_B") (pintype "input"))
      (node (ref "GATE129") (pin "C") (pinfunction "C_C") (pintype "input"))
      (node (ref "GATE130") (pin "Q") (pinfunction "Q_Q") (pintype "output"))
    )
    (net (code "133") (name "Net-(GATE127-PadC)") (class "Default")
      (node (ref "GATE127") (pin "C") (pinfunction "C_C") (pintype "input"))
      (node (ref "GATE128") (pin "Q") (pinfunction "Q_Q") (pintype "output"))
      (node (ref "GATE129") (pin "A") (pinfunction "A_A") (pintype "input"))
      (node (ref "GATE131") (pin "A") (pinfunction "A_A") (pintype "input"))
    )
    (net (code "134") (name "Net-(GATE127-PadQ)") (class "Default")
      (node (ref "GATE127") (pin "Q") (pinfunction "Q_Q") (pintype "output"))
      (node (ref "GATE128") (pin "A") (pinfunction "A_A") (pintype "input"))
    )
    (net (code "135") (name "Net-(GATE129-PadQ)") (class "Default")
      (node (ref "GATE129") (pin "Q") (pinfunction "Q_Q") (pintype "output"))
      (node (ref "GATE130") (pin "A") (pinfunction "A_A") (pintype "input"))
      (node (ref "GATE132") (pin "B") (pinfunction "B_B") (pintype "input"))
    )
    (net (code "136") (name "Net-(GATE130-PadB)") (class "Default")
      (node (ref "GATE130") (pin "B") (pinfunction "B_B") (pintype "input"))
      (node (ref "GATE131") (pin "B") (pinfunction "B_B") (pintype "input"))
      (node (ref "GATE132") (pin "Q") (pinfunction "Q_Q") (pintype "output"))
      (node (ref "GATE162") (pin "B") (pinfunction "B_B") (pintype "input"))
    )
    (net (code "137") (name "Net-(GATE133-PadB)") (class "Default")
      (node (ref "GATE133") (pin "B") (pinfunction "B_B") (pintype "input"))
      (node (ref "GATE135") (pin "C") (pinfunction "C_C") (pintype "input"))
      (node (ref "GATE136") (pin "Q") (pinfunction "Q_Q") (pintype "output"))
    )
    (net (code "138") (name "Net-(GATE133-PadC)") (class "Default")
      (node (ref "GATE133") (pin "C") (pinfunction "C_C") (pintype "input"))
      (node (ref "GATE134") (pin "Q") (pinfunction "Q_Q") (pintype "output"))
      (node (ref "GATE135") (pin "A") (pinfunction "A_A") (pintype "input"))
      (node (ref "GATE137") (pin "A") (pinfunction "A_A") (pintype "input"))
    )
    (net (code "139") (name "Net-(GATE133-PadQ)") (class "Default")
      (node (ref "GATE133") (pin "Q") (pinfunction "Q_Q") (pintype "output"))
      (node (ref "GATE134") (pin "A") (pinfunction "A_A") (pintype "input"))
    )
    (net (code "140") (name "Net-(GATE135-PadQ)") (class "Default")
      (node (ref "GATE135") (pin "Q") (pinfunction "Q_Q") (pintype "output"))
      (node (ref "GATE136") (pin "A") (pinfunction "A_A") (pintype "input"))
      (node (ref "GATE138") (pin "B") (pinfunction "B_B") (pintype "input"))
    )
    (net (code "141") (name "Net-(GATE136-PadB)") (class "Default")
      (node (ref "GATE136") (pin "B") (pinfunction "B_B") (pintype "input"))
      (node (ref "GATE137") (pin "B") (pinfunction "B_B") (pintype "input"))
      (node (ref "GATE138") (pin "Q") (pinfunction "Q_Q") (pintype "output"))
      (node (ref "GATE139") (pin "A") (pinfunction "A_A") (pintype "input"))
    )
    (net (code "142") (name "Net-(GATE139-PadQ)") (class "Default")
      (node (ref "GATE139") (pin "Q") (pinfunction "Q_Q") (pintype "output"))
      (node (ref "GATE140") (pin "A") (pinfunction "A_A") (pintype "input"))
    )
    (net (code "143") (name "Net-(GATE140-PadB)") (class "Default")
      (node (ref "GATE140") (pin "B") (pinfunction "B_B") (pintype "input"))
      (node (ref "GATE141") (pin "Q") (pinfunction "Q_Q") (pintype "output"))
      (node (ref "GATE142") (pin "B") (pinfunction "B_B") (pintype "input"))
    )
    (net (code "144") (name "Net-(GATE140-PadQ)") (class "Default")
      (node (ref "GATE140") (pin "Q") (pinfunction "Q_Q") (pintype "output"))
      (node (ref "GATE141") (pin "A") (pinfunction "A_A") (pintype "input"))
      (node (ref "GATE144") (pin "A") (pinfunction "A_A") (pintype "input"))
    )
    (net (code "145") (name "Net-(GATE142-PadA)") (class "Default")
      (node (ref "GATE142") (pin "A") (pinfunction "A_A") (pintype "input"))
      (node (ref "GATE158") (pin "A") (pinfunction "A_A") (pintype "input"))
      (node (ref "GATE162") (pin "Q") (pinfunction "Q_Q") (pintype "output"))
    )
    (net (code "146") (name "Net-(GATE142-PadQ)") (class "Default")
      (node (ref "GATE142") (pin "Q") (pinfunction "Q_Q") (pintype "output"))
      (node (ref "GATE143") (pin "A") (pinfunction "A_A") (pintype "input"))
    )
    (net (code "147") (name "Net-(GATE144-PadQ)") (class "Default")
      (node (ref "GATE144") (pin "Q") (pinfunction "Q_Q") (pintype "output"))
      (node (ref "GATE145") (pin "B") (pinfunction "B_B") (pintype "input"))
    )
    (net (code "148") (name "Net-(GATE145-PadQ)") (class "Default")
      (node (ref "GATE145") (pin "Q") (pinfunction "Q_Q") (pintype "output"))
      (node (ref "GATE147") (pin "B") (pinfunction "B_B") (pintype "input"))
      (node (ref "GATE148") (pin "B") (pinfunction "B_B") (pintype "input"))
    )
    (net (code "149") (name "Net-(GATE146-PadB)") (class "Default")
      (node (ref "GATE146") (pin "B") (pinfunction "B_B") (pintype "input"))
      (node (ref "GATE148") (pin "C") (pinfunction "C_C") (pintype "input"))
      (node (ref "GATE149") (pin "Q") (pinfunction "Q_Q") (pintype "output"))
    )
    (net (code "150") (name "Net-(GATE146-PadC)") (class "Default")
      (node (ref "GATE146") (pin "C") (pinfunction "C_C") (pintype "input"))
      (node (ref "GATE147") (pin "Q") (pinfunction "Q_Q") (pintype "output"))
      (node (ref "GATE148") (pin "A") (pinfunction "A_A") (pintype "input"))
      (node (ref "GATE150") (pin "A") (pinfunction "A_A") (pintype "input"))
    )
    (net (code "151") (name "Net-(GATE146-PadQ)") (class "Default")
      (node (ref "GATE146") (pin "Q") (pinfunction "Q_Q") (pintype "output"))
      (node (ref "GATE147") (pin "A") (pinfunction "A_A") (pintype "input"))
    )
    (net (code "152") (name "Net-(GATE148-PadQ)") (class "Default")
      (node (ref "GATE148") (pin "Q") (pinfunction "Q_Q") (pintype "output"))
      (node (ref "GATE149") (pin "A") (pinfunction "A_A") (pintype "input"))
      (node (ref "GATE151") (pin "B") (pinfunction "B_B") (pintype "input"))
    )
    (net (code "153") (name "Net-(GATE149-PadB)") (class "Default")
      (node (ref "GATE149") (pin "B") (pinfunction "B_B") (pintype "input"))
      (node (ref "GATE150") (pin "B") (pinfunction "B_B") (pintype "input"))
      (node (ref "GATE151") (pin "Q") (pinfunction "Q_Q") (pintype "output"))
    )
    (net (code "154") (name "Net-(GATE152-PadB)") (class "Default")
      (node (ref "GATE152") (pin "B") (pinfunction "B_B") (pintype "input"))
      (node (ref "GATE154") (pin "C") (pinfunction "C_C") (pintype "input"))
      (node (ref "GATE155") (pin "Q") (pinfunction "Q_Q") (pintype "output"))
    )
    (net (code "155") (name "Net-(GATE152-PadC)") (class "Default")
      (node (ref "GATE152") (pin "C") (pinfunction "C_C") (pintype "input"))
      (node (ref "GATE153") (pin "Q") (pinfunction "Q_Q") (pintype "output"))
      (node (ref "GATE154") (pin "A") (pinfunction "A_A") (pintype "input"))
      (node (ref "GATE156") (pin "A") (pinfunction "A_A") (pintype "input"))
    )
    (net (code "156") (name "Net-(GATE152-PadQ)") (class "Default")
      (node (ref "GATE152") (pin "Q") (pinfunction "Q_Q") (pintype "output"))
      (node (ref "GATE153") (pin "A") (pinfunction "A_A") (pintype "input"))
    )
    (net (code "157") (name "Net-(GATE154-PadQ)") (class "Default")
      (node (ref "GATE154") (pin "Q") (pinfunction "Q_Q") (pintype "output"))
      (node (ref "GATE155") (pin "A") (pinfunction "A_A") (pintype "input"))
      (node (ref "GATE157") (pin "B") (pinfunction "B_B") (pintype "input"))
    )
    (net (code "158") (name "Net-(GATE155-PadB)") (class "Default")
      (node (ref "GATE155") (pin "B") (pinfunction "B_B") (pintype "input"))
      (node (ref "GATE156") (pin "B") (pinfunction "B_B") (pintype "input"))
      (node (ref "GATE157") (pin "Q") (pinfunction "Q_Q") (pintype "output"))
      (node (ref "GATE162") (pin "A") (pinfunction "A_A") (pintype "input"))
    )
    (net (code "159") (name "Net-(GATE158-PadB)") (class "Default")
      (node (ref "GATE158") (pin "B") (pinfunction "B_B") (pintype "input"))
      (node (ref "GATE159") (pin "Q") (pinfunction "Q_Q") (pintype "output"))
      (node (ref "GATE160") (pin "A") (pinfunction "A_A") (pintype "input"))
    )
    (net (code "160") (name "Net-(GATE160-PadQ)") (class "Default")
      (node (ref "GATE160") (pin "Q") (pinfunction "Q_Q") (pintype "output"))
      (node (ref "GATE161") (pin "A") (pinfunction "A_A") (pintype "input"))
    )
    (net (code "161") (name "Net-(Q1-G)") (class "Default")
      (node (ref "C2") (pin "2") (pinfunction "2_2") (pintype "passive"))
      (node (ref "Q1") (pin "2") (pinfunction "G_2") (pintype "passive"))
      (node (ref "R2") (pin "2") (pinfunction "2_2") (pintype "passive"))
    )
    (net (code "162") (name "Net-(Q2-G)") (class "Default")
      (node (ref "C3") (pin "2") (pinfunction "2_2") (pintype "passive"))
      (node (ref "Q2") (pin "2") (pinfunction "G_2") (pintype "passive"))
      (node (ref "R5") (pin "2") (pinfunction "2_2") (pintype "passive"))
    )
    (net (code "163") (name "Net-(R1-Pad2)") (class "Default")
      (node (ref "R1") (pin "2") (pinfunction "2_2") (pintype "passive"))
      (node (ref "R2") (pin "1") (pinfunction "1_1") (pintype "passive"))
      (node (ref "SW1") (pin "1") (pinfunction "1_1") (pintype "passive"))
      (node (ref "SW1") (pin "2") (pinfunction "2_2") (pintype "passive"))
    )
    (net (code "164") (name "Net-(R4-Pad2)") (class "Default")
      (node (ref "R4") (pin "2") (pinfunction "2_2") (pintype "passive"))
      (node (ref "R5") (pin "1") (pinfunction "1_1") (pintype "passive"))
      (node (ref "SW2") (pin "1") (pinfunction "1_1") (pintype "passive"))
      (node (ref "SW2") (pin "2") (pinfunction "2_2") (pintype "passive"))
    )
    (net (code "165") (name "SEC_TENS_A") (class "Default")
      (node (ref "A_BUS") (pin "5") (pinfunction "5_5") (pintype "passive"))
      (node (ref "GATE38") (pin "Q") (pinfunction "Q_Q") (pintype "output"))
      (node (ref "GATE39") (pin "A") (pinfunction "A_A") (pintype "input"))
      (node (ref "GATE41") (pin "B") (pinfunction "B_B") (pintype "input"))
      (node (ref "GATE42") (pin "B") (pinfunction "B_B") (pintype "input"))
    )
    (net (code "166") (name "SEC_TENS_B") (class "Default")
      (node (ref "A_BUS") (pin "6") (pinfunction "6_6") (pintype "passive"))
      (node (ref "GATE44") (pin "Q") (pinfunction "Q_Q") (pintype "output"))
      (node (ref "GATE45") (pin "A") (pinfunction "A_A") (pintype "input"))
      (node (ref "GATE47") (pin "B") (pinfunction "B_B") (pintype "input"))
      (node (ref "GATE48") (pin "B") (pinfunction "B_B") (pintype "input"))
    )
    (net (code "167") (name "SEC_TENS_C") (class "Default")
      (node (ref "A_BUS") (pin "7") (pinfunction "7_7") (pintype "passive"))
      (node (ref "GATE50") (pin "Q") (pinfunction "Q_Q") (pintype "output"))
      (node (ref "GATE51") (pin "A") (pinfunction "A_A") (pintype "input"))
    )
    (net (code "168") (name "SEC_UNIT_A") (class "Default")
      (node (ref "A_BUS") (pin "1") (pinfunction "1_1") (pintype "passive"))
      (node (ref "GATE10") (pin "B") (pinfunction "B_B") (pintype "input"))
      (node (ref "GATE11") (pin "B") (pinfunction "B_B") (pintype "input"))
      (node (ref "GATE7") (pin "Q") (pinfunction "Q_Q") (pintype "output"))
      (node (ref "GATE8") (pin "A") (pinfunction "A_A") (pintype "input"))
    )
    (net (code "169") (name "SEC_UNIT_B") (class "Default")
      (node (ref "A_BUS") (pin "2") (pinfunction "2_2") (pintype "passive"))
      (node (ref "GATE13") (pin "Q") (pinfunction "Q_Q") (pintype "output"))
      (node (ref "GATE14") (pin "A") (pinfunction "A_A") (pintype "input"))
      (node (ref "GATE16") (pin "B") (pinfunction "B_B") (pintype "input"))
      (node (ref "GATE17") (pin "B") (pinfunction "B_B") (pintype "input"))
    )
    (net (code "170") (name "SEC_UNIT_C") (class "Default")
      (node (ref "A_BUS") (pin "3") (pinfunction "3_3") (pintype "passive"))
      (node (ref "GATE19") (pin "Q") (pinfunction "Q_Q") (pintype "output"))
      (node (ref "GATE20") (pin "A") (pinfunction "A_A") (pintype "input"))
      (node (ref "GATE22") (pin "B") (pinfunction "B_B") (pintype "input"))
      (node (ref "GATE23") (pin "B") (pinfunction "B_B") (pintype "input"))
    )
    (net (code "171") (name "SEC_UNIT_D") (class "Default")
      (node (ref "A_BUS") (pin "4") (pinfunction "4_4") (pintype "passive"))
      (node (ref "GATE25") (pin "Q") (pinfunction "Q_Q") (pintype "output"))
      (node (ref "GATE26") (pin "A") (pinfunction "A_A") (pintype "input"))
    )
    (net (code "172") (name "VDD") (class "Default")
      (node (ref "A_BUS") (pin "38") (pinfunction "38_38") (pintype "passive"))
      (node (ref "A_BUS") (pin "40") (pinfunction "40_40") (pintype "passive"))
      (node (ref "C1") (pin "+") (pinfunction "+_+") (pintype "passive"))
      (node (ref "CON1") (pin "1") (pinfunction "1_1") (pintype "passive"))
      (node (ref "CON1") (pin "2") (pinfunction "2_2") (pintype "passive"))
      (node (ref "R1") (pin "1") (pinfunction "1_1") (pintype "passive"))
      (node (ref "R3") (pin "2") (pinfunction "2_2") (pintype "passive"))
      (node (ref "R4") (pin "1") (pinfunction "1_1") (pintype "passive"))
      (node (ref "R6") (pin "2") (pinfunction "2_2") (pintype "passive"))
    )
    (net (code "173") (name "VSS") (class "Default")
      (node (ref "A_BUS") (pin "37") (pinfunction "37_37") (pintype "passive"))
      (node (ref "A_BUS") (pin "39") (pinfunction "39_39") (pintype "passive"))
      (node (ref "C1") (pin "-") (pinfunction "-_-") (pintype "passive"))
      (node (ref "C2") (pin "1") (pinfunction "1_1") (pintype "passive"))
      (node (ref "C3") (pin "1") (pinfunction "1_1") (pintype "passive"))
      (node (ref "CON1") (pin "3") (pinfunction "3_3") (pintype "passive"))
      (node (ref "CON1") (pin "4") (pinfunction "4_4") (pintype "passive"))
      (node (ref "Q1") (pin "1") (pinfunction "S_1") (pintype "passive"))
      (node (ref "Q2") (pin "1") (pinfunction "S_1") (pintype "passive"))
      (node (ref "SW1") (pin "3") (pinfunction "3_3") (pintype "passive"))
      (node (ref "SW1") (pin "4") (pinfunction "4_4") (pintype "passive"))
      (node (ref "SW2") (pin "3") (pinfunction "3_3") (pintype "passive"))
      (node (ref "SW2") (pin "4") (pinfunction "4_4") (pintype "passive"))
    )
    (net (code "174") (name "unconnected-(A_BUS-Pad21)") (class "Default")
      (node (ref "A_BUS") (pin "21") (pinfunction "21_21") (pintype "passive"))
    )
    (net (code "175") (name "unconnected-(A_BUS-Pad22)") (class "Default")
      (node (ref "A_BUS") (pin "22") (pinfunction "22_22") (pintype "passive"))
    )
    (net (code "176") (name "unconnected-(A_BUS-Pad23)") (class "Default")
      (node (ref "A_BUS") (pin "23") (pinfunction "23_23") (pintype "passive"))
    )
    (net (code "177") (name "unconnected-(A_BUS-Pad24)") (class "Default")
      (node (ref "A_BUS") (pin "24") (pinfunction "24_24") (pintype "passive"))
    )
    (net (code "178") (name "unconnected-(A_BUS-Pad25)") (class "Default")
      (node (ref "A_BUS") (pin "25") (pinfunction "25_25") (pintype "passive"))
    )
    (net (code "179") (name "unconnected-(A_BUS-Pad26)") (class "Default")
      (node (ref "A_BUS") (pin "26") (pinfunction "26_26") (pintype "passive"))
    )
    (net (code "180") (name "unconnected-(A_BUS-Pad27)") (class "Default")
      (node (ref "A_BUS") (pin "27") (pinfunction "27_27") (pintype "passive"))
    )
    (net (code "181") (name "unconnected-(A_BUS-Pad28)") (class "Default")
      (node (ref "A_BUS") (pin "28") (pinfunction "28_28") (pintype "passive"))
    )
    (net (code "182") (name "unconnected-(A_BUS-Pad30)") (class "Default")
      (node (ref "A_BUS") (pin "30") (pinfunction "30_30") (pintype "passive"))
    )
    (net (code "183") (name "unconnected-(A_BUS-Pad36)") (class "Default")
      (node (ref "A_BUS") (pin "36") (pinfunction "36_36") (pintype "passive"))
    )
    (net (code "184") (name "unconnected-(CON1-Pad8)") (class "Default")
      (node (ref "CON1") (pin "8") (pinfunction "8_8") (pintype "passive"))
    )
  )
)
